# design.net
KiCad netlist of a schematic drawn in Altium Designer
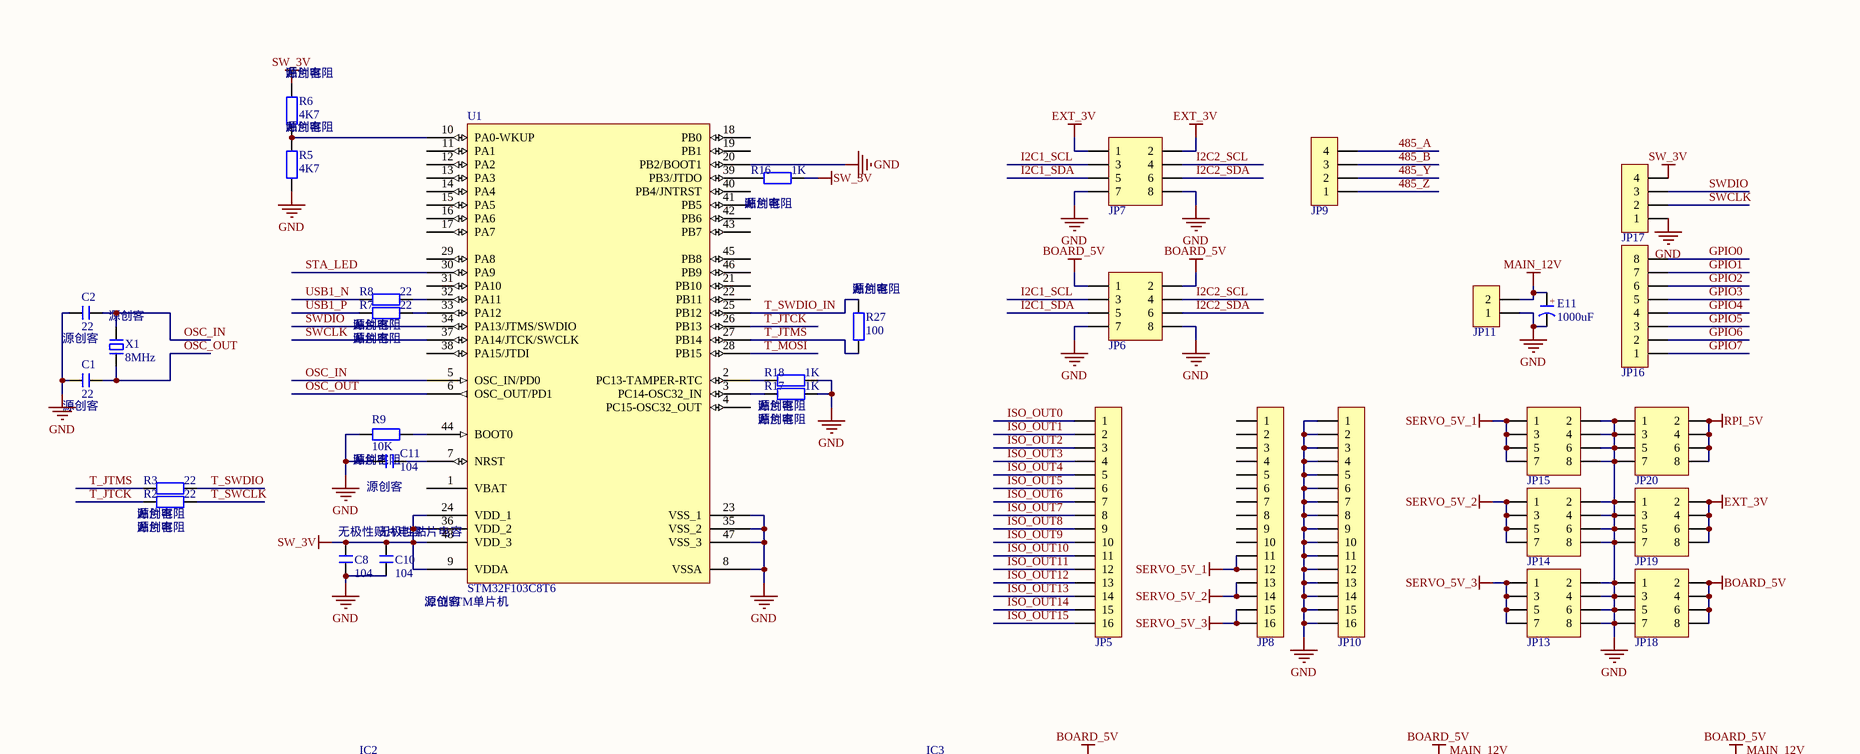
[diagram p0: 主板.SchDoc, top left]
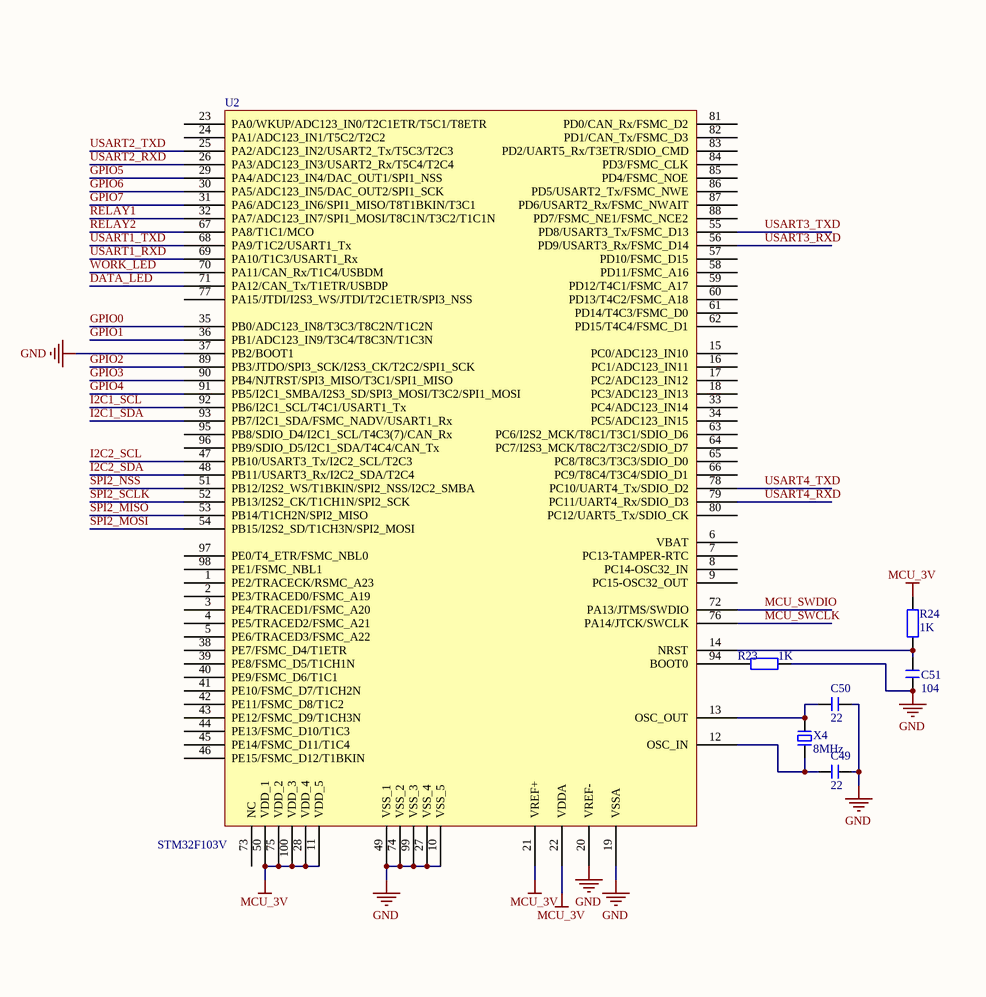
[diagram p1: 主板.SchDoc, top right]
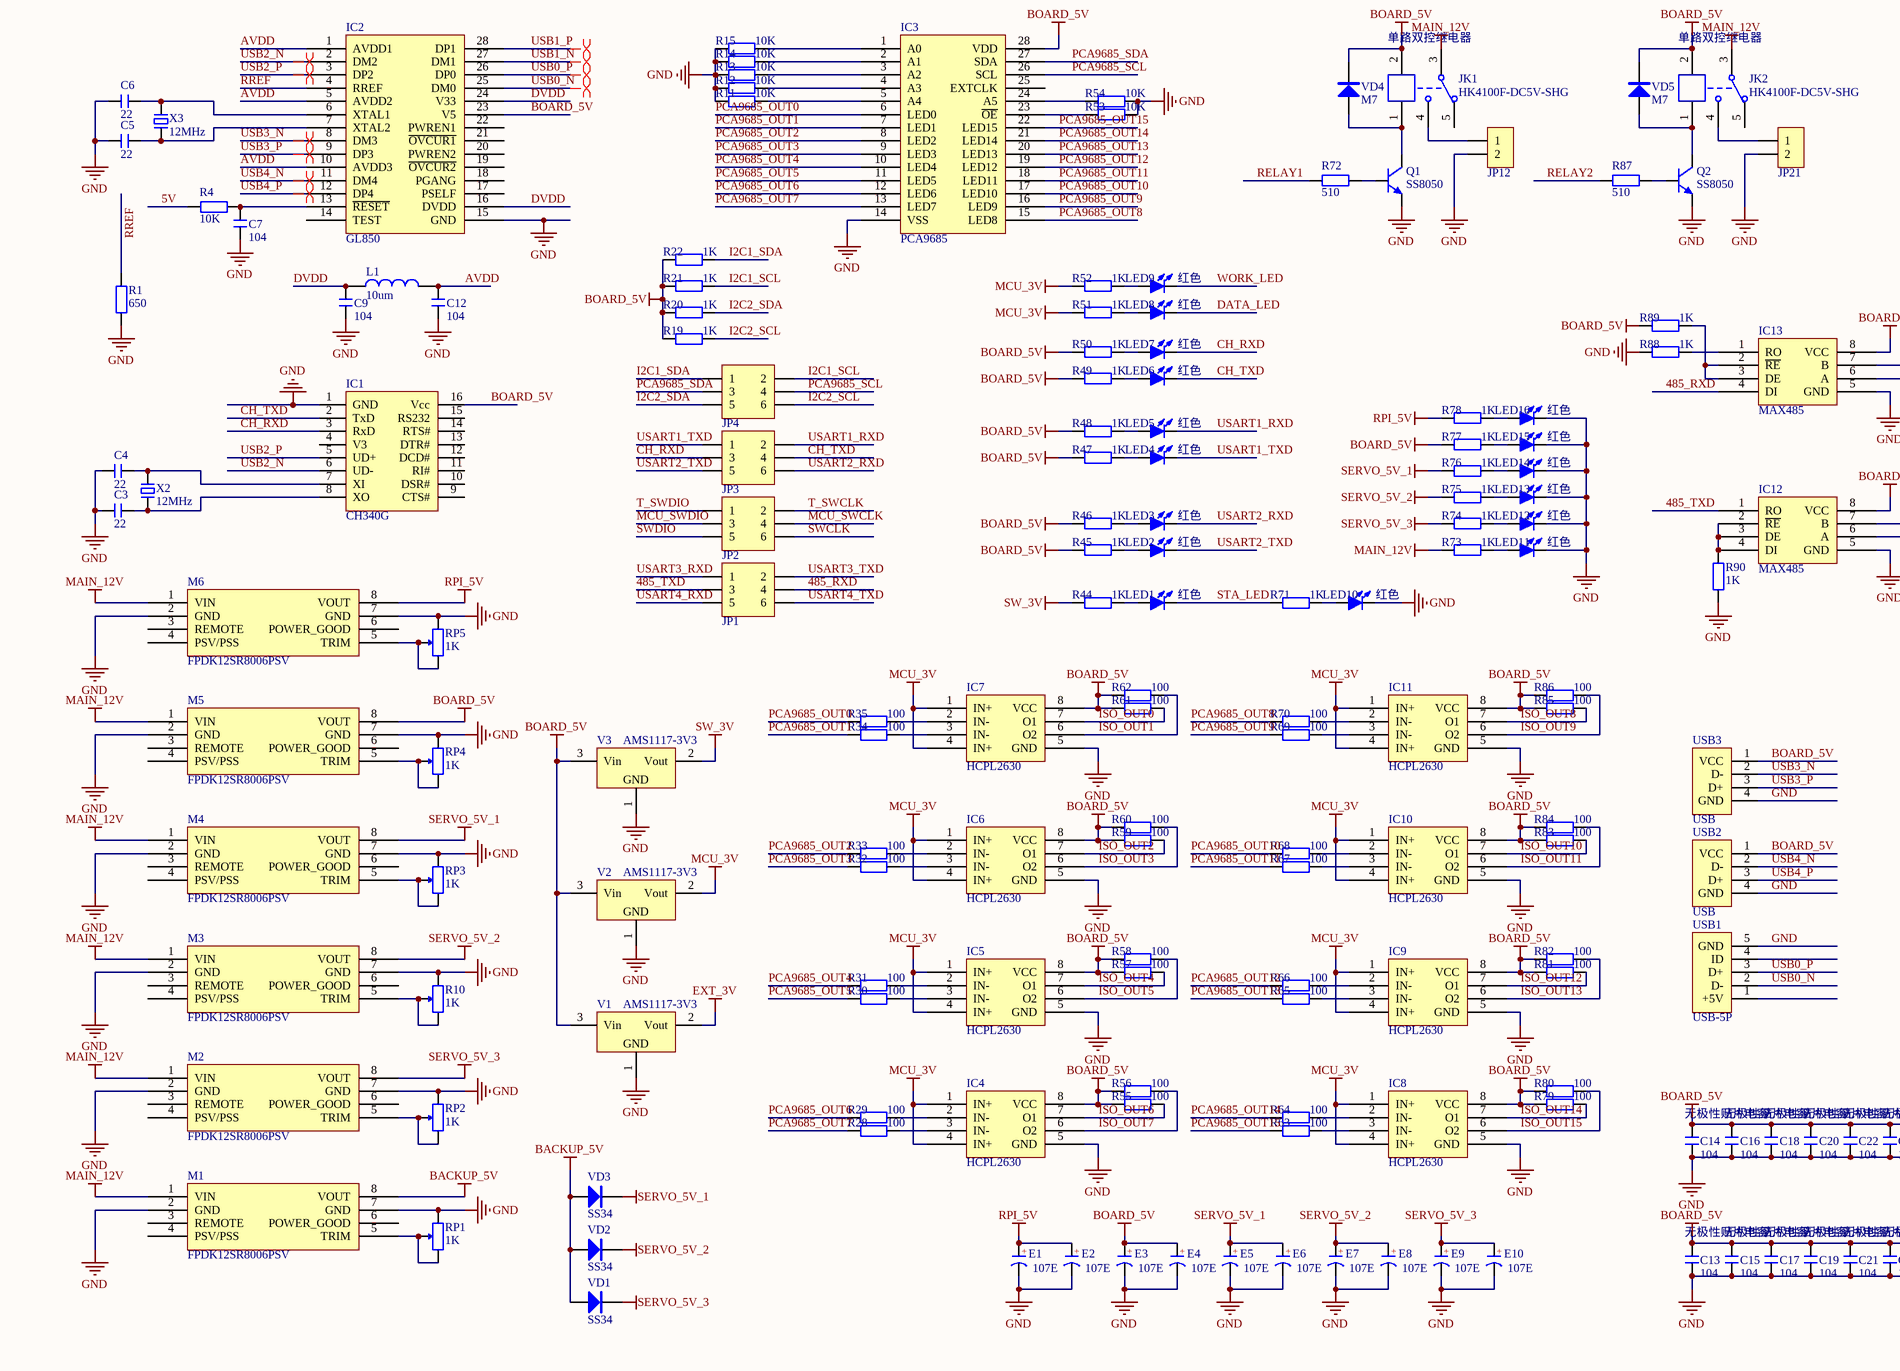
[diagram p2: 主板.SchDoc, bottom left]
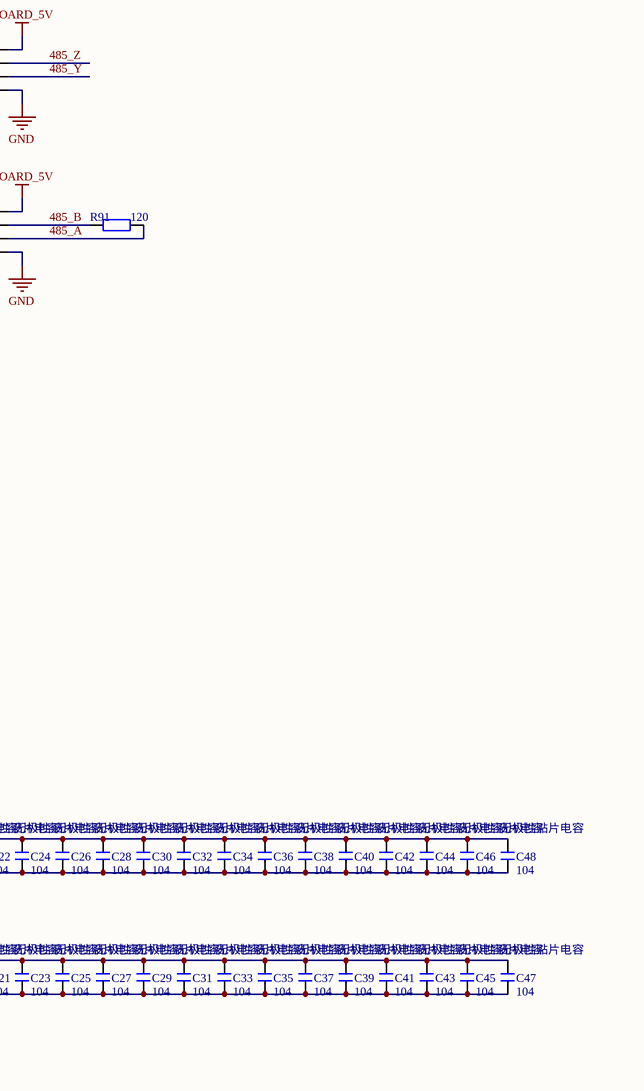
[diagram p3: 主板.SchDoc, bottom right]

(export (version "E")
  (design (tool "Eeschema 10.0.6"))
  (components
    (comp (ref "C1") (value "22") (description "无极性贴片电容") (libsource (lib "电阻-电容-电感") (part "C")))
    (comp (ref "C2") (value "22") (description "无极性贴片电容") (libsource (lib "电阻-电容-电感") (part "C")))
    (comp (ref "C3") (value "22") (description "无极性贴片电容") (libsource (lib "电阻-电容-电感") (part "C")))
    (comp (ref "C4") (value "22") (description "无极性贴片电容") (libsource (lib "电阻-电容-电感") (part "C")))
    (comp (ref "C5") (value "22") (description "无极性贴片电容") (libsource (lib "电阻-电容-电感") (part "C")))
    (comp (ref "C6") (value "22") (description "无极性贴片电容") (libsource (lib "电阻-电容-电感") (part "C")))
    (comp (ref "C7") (value "104") (description "无极性贴片电容") (libsource (lib "电阻-电容-电感") (part "C")))
    (comp (ref "C8") (value "104") (description "无极性贴片电容") (libsource (lib "电阻-电容-电感") (part "C")))
    (comp (ref "C9") (value "104") (description "无极性贴片电容") (libsource (lib "电阻-电容-电感") (part "C")))
    (comp (ref "C10") (value "104") (description "无极性贴片电容") (libsource (lib "电阻-电容-电感") (part "C")))
    (comp (ref "C11") (value "104") (description "无极性贴片电容") (libsource (lib "电阻-电容-电感") (part "C")))
    (comp (ref "C12") (value "104") (description "无极性贴片电容") (libsource (lib "电阻-电容-电感") (part "C")))
    (comp (ref "C13") (value "104") (description "无极性贴片电容") (libsource (lib "电阻-电容-电感") (part "C")))
    (comp (ref "C14") (value "104") (description "无极性贴片电容") (libsource (lib "电阻-电容-电感") (part "C")))
    (comp (ref "C15") (value "104") (description "无极性贴片电容") (libsource (lib "电阻-电容-电感") (part "C")))
    (comp (ref "C16") (value "104") (description "无极性贴片电容") (libsource (lib "电阻-电容-电感") (part "C")))
    (comp (ref "C17") (value "104") (description "无极性贴片电容") (libsource (lib "电阻-电容-电感") (part "C")))
    (comp (ref "C18") (value "104") (description "无极性贴片电容") (libsource (lib "电阻-电容-电感") (part "C")))
    (comp (ref "C19") (value "104") (description "无极性贴片电容") (libsource (lib "电阻-电容-电感") (part "C")))
    (comp (ref "C20") (value "104") (description "无极性贴片电容") (libsource (lib "电阻-电容-电感") (part "C")))
    (comp (ref "C21") (value "104") (description "无极性贴片电容") (libsource (lib "电阻-电容-电感") (part "C")))
    (comp (ref "C22") (value "104") (description "无极性贴片电容") (libsource (lib "电阻-电容-电感") (part "C")))
    (comp (ref "C23") (value "104") (description "无极性贴片电容") (libsource (lib "电阻-电容-电感") (part "C")))
    (comp (ref "C24") (value "104") (description "无极性贴片电容") (libsource (lib "电阻-电容-电感") (part "C")))
    (comp (ref "C25") (value "104") (description "无极性贴片电容") (libsource (lib "电阻-电容-电感") (part "C")))
    (comp (ref "C26") (value "104") (description "无极性贴片电容") (libsource (lib "电阻-电容-电感") (part "C")))
    (comp (ref "C27") (value "104") (description "无极性贴片电容") (libsource (lib "电阻-电容-电感") (part "C")))
    (comp (ref "C28") (value "104") (description "无极性贴片电容") (libsource (lib "电阻-电容-电感") (part "C")))
    (comp (ref "C29") (value "104") (description "无极性贴片电容") (libsource (lib "电阻-电容-电感") (part "C")))
    (comp (ref "C30") (value "104") (description "无极性贴片电容") (libsource (lib "电阻-电容-电感") (part "C")))
    (comp (ref "C31") (value "104") (description "无极性贴片电容") (libsource (lib "电阻-电容-电感") (part "C")))
    (comp (ref "C32") (value "104") (description "无极性贴片电容") (libsource (lib "电阻-电容-电感") (part "C")))
    (comp (ref "C33") (value "104") (description "无极性贴片电容") (libsource (lib "电阻-电容-电感") (part "C")))
    (comp (ref "C34") (value "104") (description "无极性贴片电容") (libsource (lib "电阻-电容-电感") (part "C")))
    (comp (ref "C35") (value "104") (description "无极性贴片电容") (libsource (lib "电阻-电容-电感") (part "C")))
    (comp (ref "C36") (value "104") (description "无极性贴片电容") (libsource (lib "电阻-电容-电感") (part "C")))
    (comp (ref "C37") (value "104") (description "无极性贴片电容") (libsource (lib "电阻-电容-电感") (part "C")))
    (comp (ref "C38") (value "104") (description "无极性贴片电容") (libsource (lib "电阻-电容-电感") (part "C")))
    (comp (ref "C39") (value "104") (description "无极性贴片电容") (libsource (lib "电阻-电容-电感") (part "C")))
    (comp (ref "C40") (value "104") (description "无极性贴片电容") (libsource (lib "电阻-电容-电感") (part "C")))
    (comp (ref "C41") (value "104") (description "无极性贴片电容") (libsource (lib "电阻-电容-电感") (part "C")))
    (comp (ref "C42") (value "104") (description "无极性贴片电容") (libsource (lib "电阻-电容-电感") (part "C")))
    (comp (ref "C43") (value "104") (description "无极性贴片电容") (libsource (lib "电阻-电容-电感") (part "C")))
    (comp (ref "C44") (value "104") (description "无极性贴片电容") (libsource (lib "电阻-电容-电感") (part "C")))
    (comp (ref "C45") (value "104") (description "无极性贴片电容") (libsource (lib "电阻-电容-电感") (part "C")))
    (comp (ref "C46") (value "104") (description "无极性贴片电容") (libsource (lib "电阻-电容-电感") (part "C")))
    (comp (ref "C47") (value "104") (description "无极性贴片电容") (libsource (lib "电阻-电容-电感") (part "C")))
    (comp (ref "C48") (value "104") (description "无极性贴片电容") (libsource (lib "电阻-电容-电感") (part "C")))
    (comp (ref "C49") (value "22") (description "无极性贴片电容") (libsource (lib "电阻-电容-电感") (part "C")))
    (comp (ref "C50") (value "22") (description "无极性贴片电容") (libsource (lib "电阻-电容-电感") (part "C")))
    (comp (ref "C51") (value "104") (description "无极性贴片电容") (libsource (lib "电阻-电容-电感") (part "C")))
    (comp (ref "E1") (value "107E") (description "贴片钽电容") (libsource (lib "电阻-电容-电感") (part "C-CD")))
    (comp (ref "E2") (value "107E") (description "贴片钽电容") (libsource (lib "电阻-电容-电感") (part "C-CD")))
    (comp (ref "E3") (value "107E") (description "贴片钽电容") (libsource (lib "电阻-电容-电感") (part "C-CD")))
    (comp (ref "E4") (value "107E") (description "贴片钽电容") (libsource (lib "电阻-电容-电感") (part "C-CD")))
    (comp (ref "E5") (value "107E") (description "贴片钽电容") (libsource (lib "电阻-电容-电感") (part "C-CD")))
    (comp (ref "E6") (value "107E") (description "贴片钽电容") (libsource (lib "电阻-电容-电感") (part "C-CD")))
    (comp (ref "E7") (value "107E") (description "贴片钽电容") (libsource (lib "电阻-电容-电感") (part "C-CD")))
    (comp (ref "E8") (value "107E") (description "贴片钽电容") (libsource (lib "电阻-电容-电感") (part "C-CD")))
    (comp (ref "E9") (value "107E") (description "贴片钽电容") (libsource (lib "电阻-电容-电感") (part "C-CD")))
    (comp (ref "E10") (value "107E") (description "贴片钽电容") (libsource (lib "电阻-电容-电感") (part "C-CD")))
    (comp (ref "E11") (value "1000uF") (description "直插固态电容") (libsource (lib "电阻-电容-电感") (part "C-CS")))
    (comp (ref "IC1") (value "CH340G") (description "串口转USB") (libsource (lib "IC芯片") (part "CH340G")))
    (comp (ref "IC2") (value "GL850") (description "4 Port USB HUB") (libsource (lib "ROV") (part "GL850G")))
    (comp (ref "IC3") (value "PCA9685") (libsource (lib "ROV") (part "PCA9685")))
    (comp (ref "IC4")
      (value "HCPL2630")
      (description "高速光电耦合器 10Mbit/s")
      (libsource (lib "ROV") (part "HCPL2630"))
    )
    (comp (ref "IC5")
      (value "HCPL2630")
      (description "高速光电耦合器 10Mbit/s")
      (libsource (lib "ROV") (part "HCPL2630"))
    )
    (comp (ref "IC6")
      (value "HCPL2630")
      (description "高速光电耦合器 10Mbit/s")
      (libsource (lib "ROV") (part "HCPL2630"))
    )
    (comp (ref "IC7")
      (value "HCPL2630")
      (description "高速光电耦合器 10Mbit/s")
      (libsource (lib "ROV") (part "HCPL2630"))
    )
    (comp (ref "IC8")
      (value "HCPL2630")
      (description "高速光电耦合器 10Mbit/s")
      (libsource (lib "ROV") (part "HCPL2630"))
    )
    (comp (ref "IC9")
      (value "HCPL2630")
      (description "高速光电耦合器 10Mbit/s")
      (libsource (lib "ROV") (part "HCPL2630"))
    )
    (comp (ref "IC10")
      (value "HCPL2630")
      (description "高速光电耦合器 10Mbit/s")
      (libsource (lib "ROV") (part "HCPL2630"))
    )
    (comp (ref "IC11")
      (value "HCPL2630")
      (description "高速光电耦合器 10Mbit/s")
      (libsource (lib "ROV") (part "HCPL2630"))
    )
    (comp (ref "IC12") (value "MAX485") (description "485通信芯片") (libsource (lib "ROV") (part "MAX485")))
    (comp (ref "IC13") (value "MAX485") (description "485通信芯片") (libsource (lib "ROV") (part "MAX485")))
    (comp (ref "JK1")
      (value "HK4100F-DC5V-SHG")
      (footprint "HK4100F")
      (description "单路双控继电器")
      (libsource (lib "继电器") (part "HK4100F"))
    )
    (comp (ref "JK2")
      (value "HK4100F-DC5V-SHG")
      (footprint "HK4100F")
      (description "单路双控继电器")
      (libsource (lib "继电器") (part "HK4100F"))
    )
    (comp (ref "JP1") (value "Header3X2") (description "3*2P接插件") (libsource (lib "接插件") (part "Header 3X2")))
    (comp (ref "JP2") (value "Header3X2") (description "3*2P接插件") (libsource (lib "接插件") (part "Header 3X2")))
    (comp (ref "JP3") (value "Header3X2") (description "3*2P接插件") (libsource (lib "接插件") (part "Header 3X2")))
    (comp (ref "JP4") (value "Header3X2") (description "3*2P接插件") (libsource (lib "接插件") (part "Header 3X2")))
    (comp (ref "JP5") (value "HDR-1X16") (description "16P接插件") (libsource (lib "接插件") (part "Header 16")))
    (comp (ref "JP6")
      (value "Header 4X2")
      (description "4*2P接插件")
      (libsource (lib "接插件") (part "Header 4X2"))
    )
    (comp (ref "JP7")
      (value "Header 4X2")
      (description "4*2P接插件")
      (libsource (lib "接插件") (part "Header 4X2"))
    )
    (comp (ref "JP8") (value "HDR-1X16") (description "16P接插件") (libsource (lib "接插件") (part "Header 16")))
    (comp (ref "JP9") (value "HDR-1X4") (description "4P接插件") (libsource (lib "接插件") (part "Header 4")))
    (comp (ref "JP10") (value "HDR-1X16") (description "16P接插件") (libsource (lib "接插件") (part "Header 16")))
    (comp (ref "JP11") (value "HDR-1X2") (description "2P接插件") (libsource (lib "接插件") (part "Header 2")))
    (comp (ref "JP12") (value "HDR-1X2") (description "2P接插件") (libsource (lib "") (part "Header 2_1")))
    (comp (ref "JP13")
      (value "Header 4X2")
      (description "4*2P接插件")
      (libsource (lib "接插件") (part "Header 4X2"))
    )
    (comp (ref "JP14")
      (value "Header 4X2")
      (description "4*2P接插件")
      (libsource (lib "接插件") (part "Header 4X2"))
    )
    (comp (ref "JP15")
      (value "Header 4X2")
      (description "4*2P接插件")
      (libsource (lib "接插件") (part "Header 4X2"))
    )
    (comp (ref "JP16") (value "HDR-1X8") (description "8P接插件") (libsource (lib "接插件") (part "Header 8")))
    (comp (ref "JP17") (value "HDR-1X4") (description "4P接插件") (libsource (lib "接插件") (part "Header 4")))
    (comp (ref "JP18")
      (value "Header 4X2")
      (description "4*2P接插件")
      (libsource (lib "接插件") (part "Header 4X2"))
    )
    (comp (ref "JP19")
      (value "Header 4X2")
      (description "4*2P接插件")
      (libsource (lib "接插件") (part "Header 4X2"))
    )
    (comp (ref "JP20")
      (value "Header 4X2")
      (description "4*2P接插件")
      (libsource (lib "接插件") (part "Header 4X2"))
    )
    (comp (ref "JP21") (value "HDR-1X2") (description "2P接插件") (libsource (lib "") (part "Header 2_1")))
    (comp (ref "L1") (value "10um") (description "小功率贴片电感") (libsource (lib "电阻-电容-电感") (part "L")))
    (comp (ref "LED1") (value "红色") (description "贴片LED") (libsource (lib "LED") (part "LED-SMD")))
    (comp (ref "LED2") (value "红色") (description "贴片LED") (libsource (lib "LED") (part "LED-SMD")))
    (comp (ref "LED3") (value "红色") (description "贴片LED") (libsource (lib "LED") (part "LED-SMD")))
    (comp (ref "LED4") (value "红色") (description "贴片LED") (libsource (lib "LED") (part "LED-SMD")))
    (comp (ref "LED5") (value "红色") (description "贴片LED") (libsource (lib "LED") (part "LED-SMD")))
    (comp (ref "LED6") (value "红色") (description "贴片LED") (libsource (lib "LED") (part "LED-SMD")))
    (comp (ref "LED7") (value "红色") (description "贴片LED") (libsource (lib "LED") (part "LED-SMD")))
    (comp (ref "LED8") (value "红色") (description "贴片LED") (libsource (lib "LED") (part "LED-SMD")))
    (comp (ref "LED9") (value "红色") (description "贴片LED") (libsource (lib "LED") (part "LED-SMD")))
    (comp (ref "LED10") (value "红色") (description "贴片LED") (libsource (lib "LED") (part "LED-SMD")))
    (comp (ref "LED11") (value "红色") (description "贴片LED") (libsource (lib "LED") (part "LED-SMD")))
    (comp (ref "LED12") (value "红色") (description "贴片LED") (libsource (lib "LED") (part "LED-SMD")))
    (comp (ref "LED13") (value "红色") (description "贴片LED") (libsource (lib "LED") (part "LED-SMD")))
    (comp (ref "LED14") (value "红色") (description "贴片LED") (libsource (lib "LED") (part "LED-SMD")))
    (comp (ref "LED15") (value "红色") (description "贴片LED") (libsource (lib "LED") (part "LED-SMD")))
    (comp (ref "LED16") (value "红色") (description "贴片LED") (libsource (lib "LED") (part "LED-SMD")))
    (comp (ref "M1")
      (value "FPDK12SR8006PSV")
      (footprint "FPDK12SR8006PSV")
      (description "DC-DC POWER CONVERTOR 12V-TO-5V")
      (libsource (lib "ROV") (part "FPDK12SR8006PSV"))
    )
    (comp (ref "M2")
      (value "FPDK12SR8006PSV")
      (footprint "FPDK12SR8006PSV")
      (description "DC-DC POWER CONVERTOR 12V-TO-5V")
      (libsource (lib "ROV") (part "FPDK12SR8006PSV"))
    )
    (comp (ref "M3")
      (value "FPDK12SR8006PSV")
      (footprint "FPDK12SR8006PSV")
      (description "DC-DC POWER CONVERTOR 12V-TO-5V")
      (libsource (lib "ROV") (part "FPDK12SR8006PSV"))
    )
    (comp (ref "M4")
      (value "FPDK12SR8006PSV")
      (footprint "FPDK12SR8006PSV")
      (description "DC-DC POWER CONVERTOR 12V-TO-5V")
      (libsource (lib "ROV") (part "FPDK12SR8006PSV"))
    )
    (comp (ref "M5")
      (value "FPDK12SR8006PSV")
      (footprint "FPDK12SR8006PSV")
      (description "DC-DC POWER CONVERTOR 12V-TO-5V")
      (libsource (lib "ROV") (part "FPDK12SR8006PSV"))
    )
    (comp (ref "M6")
      (value "FPDK12SR8006PSV")
      (footprint "FPDK12SR8006PSV")
      (description "DC-DC POWER CONVERTOR 12V-TO-5V")
      (libsource (lib "ROV") (part "FPDK12SR8006PSV"))
    )
    (comp (ref "Q1") (value "SS8050") (description "高频放大-NPN型") (libsource (lib "三极管") (part "8050-SMD")))
    (comp (ref "Q2") (value "SS8050") (description "高频放大-NPN型") (libsource (lib "三极管") (part "8050-SMD")))
    (comp (ref "R1") (value "650") (description "贴片电阻") (libsource (lib "电阻-电容-电感") (part "R")))
    (comp (ref "R2") (value "22") (description "贴片电阻") (libsource (lib "电阻-电容-电感") (part "R")))
    (comp (ref "R3") (value "22") (description "贴片电阻") (libsource (lib "电阻-电容-电感") (part "R")))
    (comp (ref "R4") (value "10K") (description "贴片电阻") (libsource (lib "电阻-电容-电感") (part "R")))
    (comp (ref "R5") (value "4K7") (description "贴片电阻") (libsource (lib "电阻-电容-电感") (part "R")))
    (comp (ref "R6") (value "4K7") (description "贴片电阻") (libsource (lib "电阻-电容-电感") (part "R")))
    (comp (ref "R7") (value "22") (description "贴片电阻") (libsource (lib "电阻-电容-电感") (part "R")))
    (comp (ref "R8") (value "22") (description "贴片电阻") (libsource (lib "电阻-电容-电感") (part "R")))
    (comp (ref "R9") (value "10K") (description "贴片电阻") (libsource (lib "电阻-电容-电感") (part "R")))
    (comp (ref "R10")
      (value "1K")
      (footprint "3296W")
      (description "插件单联电位器")
      (libsource (lib "电阻-电容-电感") (part "RP-ID"))
    )
    (comp (ref "R11") (value "10K") (description "贴片电阻") (libsource (lib "电阻-电容-电感") (part "R")))
    (comp (ref "R12") (value "10K") (description "贴片电阻") (libsource (lib "电阻-电容-电感") (part "R")))
    (comp (ref "R13") (value "10K") (description "贴片电阻") (libsource (lib "电阻-电容-电感") (part "R")))
    (comp (ref "R14") (value "10K") (description "贴片电阻") (libsource (lib "电阻-电容-电感") (part "R")))
    (comp (ref "R15") (value "10K") (description "贴片电阻") (libsource (lib "电阻-电容-电感") (part "R")))
    (comp (ref "R16") (value "1K") (description "贴片电阻") (libsource (lib "电阻-电容-电感") (part "R")))
    (comp (ref "R17") (value "1K") (description "贴片电阻") (libsource (lib "电阻-电容-电感") (part "R")))
    (comp (ref "R18") (value "1K") (description "贴片电阻") (libsource (lib "电阻-电容-电感") (part "R")))
    (comp (ref "R19") (value "1K") (description "贴片电阻") (libsource (lib "电阻-电容-电感") (part "R")))
    (comp (ref "R20") (value "1K") (description "贴片电阻") (libsource (lib "电阻-电容-电感") (part "R")))
    (comp (ref "R21") (value "1K") (description "贴片电阻") (libsource (lib "电阻-电容-电感") (part "R")))
    (comp (ref "R22") (value "1K") (description "贴片电阻") (libsource (lib "电阻-电容-电感") (part "R")))
    (comp (ref "R23") (value "1K") (description "贴片电阻") (libsource (lib "电阻-电容-电感") (part "R")))
    (comp (ref "R24") (value "1K") (description "贴片电阻") (libsource (lib "电阻-电容-电感") (part "R")))
    (comp (ref "R27") (value "100") (description "贴片电阻") (libsource (lib "电阻-电容-电感") (part "R")))
    (comp (ref "R28") (value "100") (description "贴片电阻") (libsource (lib "电阻-电容-电感") (part "R")))
    (comp (ref "R29") (value "100") (description "贴片电阻") (libsource (lib "电阻-电容-电感") (part "R")))
    (comp (ref "R30") (value "100") (description "贴片电阻") (libsource (lib "电阻-电容-电感") (part "R")))
    (comp (ref "R31") (value "100") (description "贴片电阻") (libsource (lib "电阻-电容-电感") (part "R")))
    (comp (ref "R32") (value "100") (description "贴片电阻") (libsource (lib "电阻-电容-电感") (part "R")))
    (comp (ref "R33") (value "100") (description "贴片电阻") (libsource (lib "电阻-电容-电感") (part "R")))
    (comp (ref "R34") (value "100") (description "贴片电阻") (libsource (lib "电阻-电容-电感") (part "R")))
    (comp (ref "R35") (value "100") (description "贴片电阻") (libsource (lib "电阻-电容-电感") (part "R")))
    (comp (ref "R44") (value "1K") (description "贴片电阻") (libsource (lib "电阻-电容-电感") (part "R")))
    (comp (ref "R45") (value "1K") (description "贴片电阻") (libsource (lib "电阻-电容-电感") (part "R")))
    (comp (ref "R46") (value "1K") (description "贴片电阻") (libsource (lib "电阻-电容-电感") (part "R")))
    (comp (ref "R47") (value "1K") (description "贴片电阻") (libsource (lib "电阻-电容-电感") (part "R")))
    (comp (ref "R48") (value "1K") (description "贴片电阻") (libsource (lib "电阻-电容-电感") (part "R")))
    (comp (ref "R49") (value "1K") (description "贴片电阻") (libsource (lib "电阻-电容-电感") (part "R")))
    (comp (ref "R50") (value "1K") (description "贴片电阻") (libsource (lib "电阻-电容-电感") (part "R")))
    (comp (ref "R51") (value "1K") (description "贴片电阻") (libsource (lib "电阻-电容-电感") (part "R")))
    (comp (ref "R52") (value "1K") (description "贴片电阻") (libsource (lib "电阻-电容-电感") (part "R")))
    (comp (ref "R53") (value "10K") (description "贴片电阻") (libsource (lib "电阻-电容-电感") (part "R")))
    (comp (ref "R54") (value "10K") (description "贴片电阻") (libsource (lib "电阻-电容-电感") (part "R")))
    (comp (ref "R55") (value "100") (description "贴片电阻") (libsource (lib "电阻-电容-电感") (part "R")))
    (comp (ref "R56") (value "100") (description "贴片电阻") (libsource (lib "电阻-电容-电感") (part "R")))
    (comp (ref "R57") (value "100") (description "贴片电阻") (libsource (lib "电阻-电容-电感") (part "R")))
    (comp (ref "R58") (value "100") (description "贴片电阻") (libsource (lib "电阻-电容-电感") (part "R")))
    (comp (ref "R59") (value "100") (description "贴片电阻") (libsource (lib "电阻-电容-电感") (part "R")))
    (comp (ref "R60") (value "100") (description "贴片电阻") (libsource (lib "电阻-电容-电感") (part "R")))
    (comp (ref "R61") (value "100") (description "贴片电阻") (libsource (lib "电阻-电容-电感") (part "R")))
    (comp (ref "R62") (value "100") (description "贴片电阻") (libsource (lib "电阻-电容-电感") (part "R")))
    (comp (ref "R63") (value "100") (description "贴片电阻") (libsource (lib "电阻-电容-电感") (part "R")))
    (comp (ref "R64") (value "100") (description "贴片电阻") (libsource (lib "电阻-电容-电感") (part "R")))
    (comp (ref "R65") (value "100") (description "贴片电阻") (libsource (lib "电阻-电容-电感") (part "R")))
    (comp (ref "R66") (value "100") (description "贴片电阻") (libsource (lib "电阻-电容-电感") (part "R")))
    (comp (ref "R67") (value "100") (description "贴片电阻") (libsource (lib "电阻-电容-电感") (part "R")))
    (comp (ref "R68") (value "100") (description "贴片电阻") (libsource (lib "电阻-电容-电感") (part "R")))
    (comp (ref "R69") (value "100") (description "贴片电阻") (libsource (lib "电阻-电容-电感") (part "R")))
    (comp (ref "R70") (value "100") (description "贴片电阻") (libsource (lib "电阻-电容-电感") (part "R")))
    (comp (ref "R71") (value "1K") (description "贴片电阻") (libsource (lib "电阻-电容-电感") (part "R")))
    (comp (ref "R72") (value "510") (description "贴片电阻") (libsource (lib "电阻-电容-电感") (part "R")))
    (comp (ref "R73") (value "1K") (description "贴片电阻") (libsource (lib "电阻-电容-电感") (part "R")))
    (comp (ref "R74") (value "1K") (description "贴片电阻") (libsource (lib "电阻-电容-电感") (part "R")))
    (comp (ref "R75") (value "1K") (description "贴片电阻") (libsource (lib "电阻-电容-电感") (part "R")))
    (comp (ref "R76") (value "1K") (description "贴片电阻") (libsource (lib "电阻-电容-电感") (part "R")))
    (comp (ref "R77") (value "1K") (description "贴片电阻") (libsource (lib "电阻-电容-电感") (part "R")))
    (comp (ref "R78") (value "1K") (description "贴片电阻") (libsource (lib "电阻-电容-电感") (part "R")))
    (comp (ref "R79") (value "100") (description "贴片电阻") (libsource (lib "电阻-电容-电感") (part "R")))
    (comp (ref "R80") (value "100") (description "贴片电阻") (libsource (lib "电阻-电容-电感") (part "R")))
    (comp (ref "R81") (value "100") (description "贴片电阻") (libsource (lib "电阻-电容-电感") (part "R")))
    (comp (ref "R82") (value "100") (description "贴片电阻") (libsource (lib "电阻-电容-电感") (part "R")))
    (comp (ref "R83") (value "100") (description "贴片电阻") (libsource (lib "电阻-电容-电感") (part "R")))
    (comp (ref "R84") (value "100") (description "贴片电阻") (libsource (lib "电阻-电容-电感") (part "R")))
    (comp (ref "R85") (value "100") (description "贴片电阻") (libsource (lib "电阻-电容-电感") (part "R")))
    (comp (ref "R86") (value "100") (description "贴片电阻") (libsource (lib "电阻-电容-电感") (part "R")))
    (comp (ref "R87") (value "510") (description "贴片电阻") (libsource (lib "电阻-电容-电感") (part "R")))
    (comp (ref "R88") (value "1K") (description "贴片电阻") (libsource (lib "电阻-电容-电感") (part "R")))
    (comp (ref "R89") (value "1K") (description "贴片电阻") (libsource (lib "电阻-电容-电感") (part "R")))
    (comp (ref "R90") (value "1K") (description "贴片电阻") (libsource (lib "电阻-电容-电感") (part "R")))
    (comp (ref "R91") (value "120") (description "贴片电阻") (libsource (lib "电阻-电容-电感") (part "R")))
    (comp (ref "RP1")
      (value "1K")
      (footprint "3296W")
      (description "插件单联电位器")
      (libsource (lib "电阻-电容-电感") (part "RP-ID"))
    )
    (comp (ref "RP2")
      (value "1K")
      (footprint "3296W")
      (description "插件单联电位器")
      (libsource (lib "电阻-电容-电感") (part "RP-ID"))
    )
    (comp (ref "RP3")
      (value "1K")
      (footprint "3296W")
      (description "插件单联电位器")
      (libsource (lib "电阻-电容-电感") (part "RP-ID"))
    )
    (comp (ref "RP4")
      (value "1K")
      (footprint "3296W")
      (description "插件单联电位器")
      (libsource (lib "电阻-电容-电感") (part "RP-ID"))
    )
    (comp (ref "RP5")
      (value "1K")
      (footprint "3296W")
      (description "插件单联电位器")
      (libsource (lib "电阻-电容-电感") (part "RP-ID"))
    )
    (comp (ref "U1")
      (value "STM32F103C8T6")
      (description "Flaah:64/RAM:20/IO:36")
      (libsource (lib "STM32系列单片机") (part "STM32F103C8T6"))
    )
    (comp (ref "U2")
      (value "STM32F103V")
      (description "32位STM单片机100引脚")
      (libsource (lib "STM32系列单片机") (part "STM32F103V"))
    )
    (comp (ref "USB1") (value "USB-5P") (description "微型USB母座") (libsource (lib "接口类") (part "USB-5P")))
    (comp (ref "USB2") (value "USB") (description "USB-A型母接口") (libsource (lib "接口类") (part "USB-A/S")))
    (comp (ref "USB3") (value "USB") (description "USB-A型母接口") (libsource (lib "接口类") (part "USB-A/S")))
    (comp (ref "V1") (value "AMS1117-3V3") (description "三端稳压芯片") (libsource (lib "IC芯片") (part "AMS1117")))
    (comp (ref "V2") (value "AMS1117-3V3") (description "三端稳压芯片") (libsource (lib "IC芯片") (part "AMS1117")))
    (comp (ref "V3") (value "AMS1117-3V3") (description "三端稳压芯片") (libsource (lib "IC芯片") (part "AMS1117")))
    (comp (ref "VD1") (value "SS34") (description "肖特基二极管") (libsource (lib "二极管-整流桥") (part "SS34")))
    (comp (ref "VD2") (value "SS34") (description "肖特基二极管") (libsource (lib "二极管-整流桥") (part "SS34")))
    (comp (ref "VD3") (value "SS34") (description "肖特基二极管") (libsource (lib "二极管-整流桥") (part "SS34")))
    (comp (ref "VD4") (value "M7") (description "整流二极管") (libsource (lib "二极管-整流桥") (part "M7")))
    (comp (ref "VD5") (value "M7") (description "整流二极管") (libsource (lib "二极管-整流桥") (part "M7")))
    (comp (ref "X1")
      (value "8MHz")
      (footprint "XTAL-49S DIP")
      (description "2脚晶振")
      (libsource (lib "保险丝-晶振") (part "XTAL-2"))
    )
    (comp (ref "X2")
      (value "12MHz")
      (footprint "XTAL-49S DIP")
      (description "2脚晶振")
      (libsource (lib "保险丝-晶振") (part "XTAL-2"))
    )
    (comp (ref "X3")
      (value "12MHz")
      (footprint "XTAL-49S DIP")
      (description "2脚晶振")
      (libsource (lib "保险丝-晶振") (part "XTAL-2"))
    )
    (comp (ref "X4")
      (value "8MHz")
      (footprint "XTAL-49S DIP")
      (description "2脚晶振")
      (libsource (lib "保险丝-晶振") (part "XTAL-2"))
    )
  )
  (nets
    (net (code "1") (name "/5V") (class "Default")
      (node (ref "R4") (pin "1") (pinfunction "1_1") (pintype "passive"))
    )
    (net (code "2") (name "/485_A") (class "Default")
      (node (ref "IC12") (pin "6") (pinfunction "A_6") (pintype "passive"))
      (node (ref "JP9") (pin "4") (pinfunction "4_4") (pintype "passive"))
      (node (ref "R91") (pin "1") (pinfunction "1_1") (pintype "passive"))
    )
    (net (code "3") (name "/485_B") (class "Default")
      (node (ref "IC12") (pin "7") (pinfunction "B_7") (pintype "passive"))
      (node (ref "JP9") (pin "3") (pinfunction "3_3") (pintype "passive"))
      (node (ref "R91") (pin "2") (pinfunction "2_2") (pintype "passive"))
    )
    (net (code "4") (name "/485_RXD") (class "Default")
      (node (ref "IC13") (pin "4") (pinfunction "DI_4") (pintype "passive"))
      (node (ref "JP1") (pin "4") (pinfunction "4_4") (pintype "passive"))
    )
    (net (code "5") (name "/485_TXD") (class "Default")
      (node (ref "IC12") (pin "1") (pinfunction "RO_1") (pintype "passive"))
      (node (ref "JP1") (pin "3") (pinfunction "3_3") (pintype "passive"))
    )
    (net (code "6") (name "/485_Y") (class "Default")
      (node (ref "IC13") (pin "6") (pinfunction "A_6") (pintype "passive"))
      (node (ref "JP9") (pin "2") (pinfunction "2_2") (pintype "passive"))
    )
    (net (code "7") (name "/485_Z") (class "Default")
      (node (ref "IC13") (pin "7") (pinfunction "B_7") (pintype "passive"))
      (node (ref "JP9") (pin "1") (pinfunction "1_1") (pintype "passive"))
    )
    (net (code "8") (name "/AVDD") (class "Default")
      (node (ref "C12") (pin "2") (pinfunction "2_2") (pintype "passive"))
      (node (ref "IC2") (pin "1") (pinfunction "AVDD1_1") (pintype "passive"))
      (node (ref "IC2") (pin "10") (pinfunction "AVDD3_10") (pintype "passive"))
      (node (ref "IC2") (pin "5") (pinfunction "AVDD2_5") (pintype "passive"))
      (node (ref "L1") (pin "2") (pinfunction "2_2") (pintype "passive"))
    )
    (net (code "9") (name "/CH_RXD") (class "Default")
      (node (ref "IC1") (pin "3") (pinfunction "RxD_3") (pintype "passive"))
      (node (ref "JP3") (pin "3") (pinfunction "3_3") (pintype "passive"))
      (node (ref "LED7") (pin "2") (pinfunction "K_2") (pintype "passive"))
    )
    (net (code "10") (name "/CH_TXD") (class "Default")
      (node (ref "IC1") (pin "2") (pinfunction "TxD_2") (pintype "passive"))
      (node (ref "JP3") (pin "4") (pinfunction "4_4") (pintype "passive"))
      (node (ref "LED6") (pin "2") (pinfunction "K_2") (pintype "passive"))
    )
    (net (code "11") (name "/DATA_LED") (class "Default")
      (node (ref "LED8") (pin "2") (pinfunction "K_2") (pintype "passive"))
      (node (ref "U2") (pin "71") (pinfunction "PA12/CAN_Tx/T1ETR/USBDP_71") (pintype "passive"))
    )
    (net (code "12") (name "/DVDD") (class "Default")
      (node (ref "C9") (pin "2") (pinfunction "2_2") (pintype "passive"))
      (node (ref "IC2") (pin "16") (pinfunction "DVDD_16") (pintype "passive"))
      (node (ref "IC2") (pin "24") (pinfunction "V33_24") (pintype "passive"))
      (node (ref "L1") (pin "1") (pinfunction "1_1") (pintype "passive"))
    )
    (net (code "13") (name "/GPIO0") (class "Default")
      (node (ref "JP16") (pin "8") (pinfunction "8_8") (pintype "passive"))
      (node (ref "U2") (pin "35") (pinfunction "PB0/ADC123_IN8/T3C3/T8C2N/T1C2N_35") (pintype "passive"))
    )
    (net (code "14") (name "/GPIO1") (class "Default")
      (node (ref "JP16") (pin "7") (pinfunction "7_7") (pintype "passive"))
      (node (ref "U2") (pin "36") (pinfunction "PB1/ADC123_IN9/T3C4/T8C3N/T1C3N_36") (pintype "passive"))
    )
    (net (code "15") (name "/GPIO2") (class "Default")
      (node (ref "JP16") (pin "6") (pinfunction "6_6") (pintype "passive"))
      (node (ref "U2") (pin "89") (pinfunction "PB3/JTDO/SPI3_SCK/I2S3_CK/T2C2/SPI1_SCK_89") (pintype "passive"))
    )
    (net (code "16") (name "/GPIO3") (class "Default")
      (node (ref "JP16") (pin "5") (pinfunction "5_5") (pintype "passive"))
      (node (ref "U2") (pin "90") (pinfunction "PB4/NJTRST/SPI3_MISO/T3C1/SPI1_MISO_90") (pintype "passive"))
    )
    (net (code "17") (name "/GPIO4") (class "Default")
      (node (ref "JP16") (pin "4") (pinfunction "4_4") (pintype "passive"))
      (node (ref "U2") (pin "91") (pinfunction "PB5/I2C1_SMBA/I2S3_SD/SPI3_MOSI/T3C2/SPI1_MOSI_91") (pintype "passive"))
    )
    (net (code "18") (name "/GPIO5") (class "Default")
      (node (ref "JP16") (pin "3") (pinfunction "3_3") (pintype "passive"))
      (node (ref "U2") (pin "29") (pinfunction "PA4/ADC123_IN4/DAC_OUT1/SPI1_NSS_29") (pintype "passive"))
    )
    (net (code "19") (name "/GPIO6") (class "Default")
      (node (ref "JP16") (pin "2") (pinfunction "2_2") (pintype "passive"))
      (node (ref "U2") (pin "30") (pinfunction "PA5/ADC123_IN5/DAC_OUT2/SPI1_SCK_30") (pintype "passive"))
    )
    (net (code "20") (name "/GPIO7") (class "Default")
      (node (ref "JP16") (pin "1") (pinfunction "1_1") (pintype "passive"))
      (node (ref "U2") (pin "31") (pinfunction "PA6/ADC123_IN6/SPI1_MISO/T8T1BKIN/T3C1_31") (pintype "passive"))
    )
    (net (code "21") (name "/I2C1_SCL") (class "Default")
      (node (ref "JP4") (pin "2") (pinfunction "2_2") (pintype "passive"))
      (node (ref "JP6") (pin "3") (pinfunction "3_3") (pintype "passive"))
      (node (ref "JP7") (pin "3") (pinfunction "3_3") (pintype "passive"))
      (node (ref "R21") (pin "1") (pinfunction "1_1") (pintype "passive"))
      (node (ref "U2") (pin "92") (pinfunction "PB6/I2C1_SCL/T4C1/USART1_Tx_92") (pintype "passive"))
    )
    (net (code "22") (name "/I2C1_SDA") (class "Default")
      (node (ref "JP4") (pin "1") (pinfunction "1_1") (pintype "passive"))
      (node (ref "JP6") (pin "5") (pinfunction "5_5") (pintype "passive"))
      (node (ref "JP7") (pin "5") (pinfunction "5_5") (pintype "passive"))
      (node (ref "R22") (pin "1") (pinfunction "1_1") (pintype "passive"))
      (node (ref "U2") (pin "93") (pinfunction "PB7/I2C1_SDA/FSMC_NADV/USART1_Rx_93") (pintype "passive"))
    )
    (net (code "23") (name "/I2C2_SCL") (class "Default")
      (node (ref "JP4") (pin "6") (pinfunction "6_6") (pintype "passive"))
      (node (ref "JP6") (pin "4") (pinfunction "4_4") (pintype "passive"))
      (node (ref "JP7") (pin "4") (pinfunction "4_4") (pintype "passive"))
      (node (ref "R19") (pin "1") (pinfunction "1_1") (pintype "passive"))
      (node (ref "U2") (pin "47") (pinfunction "PB10/USART3_Tx/I2C2_SCL/T2C3_47") (pintype "passive"))
    )
    (net (code "24") (name "/I2C2_SDA") (class "Default")
      (node (ref "JP4") (pin "5") (pinfunction "5_5") (pintype "passive"))
      (node (ref "JP6") (pin "6") (pinfunction "6_6") (pintype "passive"))
      (node (ref "JP7") (pin "6") (pinfunction "6_6") (pintype "passive"))
      (node (ref "R20") (pin "1") (pinfunction "1_1") (pintype "passive"))
      (node (ref "U2") (pin "48") (pinfunction "PB11/USART3_Rx/I2C2_SDA/T2C4_48") (pintype "passive"))
    )
    (net (code "25") (name "/ISO_OUT0") (class "Default")
      (node (ref "IC7") (pin "7") (pinfunction "O1_7") (pintype "passive"))
      (node (ref "JP5") (pin "1") (pinfunction "1_1") (pintype "passive"))
      (node (ref "R61") (pin "2") (pinfunction "2_2") (pintype "passive"))
    )
    (net (code "26") (name "/ISO_OUT1") (class "Default")
      (node (ref "IC7") (pin "6") (pinfunction "O2_6") (pintype "passive"))
      (node (ref "JP5") (pin "2") (pinfunction "2_2") (pintype "passive"))
      (node (ref "R62") (pin "2") (pinfunction "2_2") (pintype "passive"))
    )
    (net (code "27") (name "/ISO_OUT2") (class "Default")
      (node (ref "IC6") (pin "7") (pinfunction "O1_7") (pintype "passive"))
      (node (ref "JP5") (pin "3") (pinfunction "3_3") (pintype "passive"))
      (node (ref "R59") (pin "2") (pinfunction "2_2") (pintype "passive"))
    )
    (net (code "28") (name "/ISO_OUT3") (class "Default")
      (node (ref "IC6") (pin "6") (pinfunction "O2_6") (pintype "passive"))
      (node (ref "JP5") (pin "4") (pinfunction "4_4") (pintype "passive"))
      (node (ref "R60") (pin "2") (pinfunction "2_2") (pintype "passive"))
    )
    (net (code "29") (name "/ISO_OUT4") (class "Default")
      (node (ref "IC5") (pin "7") (pinfunction "O1_7") (pintype "passive"))
      (node (ref "JP5") (pin "5") (pinfunction "5_5") (pintype "passive"))
      (node (ref "R57") (pin "2") (pinfunction "2_2") (pintype "passive"))
    )
    (net (code "30") (name "/ISO_OUT5") (class "Default")
      (node (ref "IC5") (pin "6") (pinfunction "O2_6") (pintype "passive"))
      (node (ref "JP5") (pin "6") (pinfunction "6_6") (pintype "passive"))
      (node (ref "R58") (pin "2") (pinfunction "2_2") (pintype "passive"))
    )
    (net (code "31") (name "/ISO_OUT6") (class "Default")
      (node (ref "IC4") (pin "7") (pinfunction "O1_7") (pintype "passive"))
      (node (ref "JP5") (pin "7") (pinfunction "7_7") (pintype "passive"))
      (node (ref "R55") (pin "2") (pinfunction "2_2") (pintype "passive"))
    )
    (net (code "32") (name "/ISO_OUT7") (class "Default")
      (node (ref "IC4") (pin "6") (pinfunction "O2_6") (pintype "passive"))
      (node (ref "JP5") (pin "8") (pinfunction "8_8") (pintype "passive"))
      (node (ref "R56") (pin "2") (pinfunction "2_2") (pintype "passive"))
    )
    (net (code "33") (name "/ISO_OUT8") (class "Default")
      (node (ref "IC11") (pin "7") (pinfunction "O1_7") (pintype "passive"))
      (node (ref "JP5") (pin "9") (pinfunction "9_9") (pintype "passive"))
      (node (ref "R85") (pin "2") (pinfunction "2_2") (pintype "passive"))
    )
    (net (code "34") (name "/ISO_OUT9") (class "Default")
      (node (ref "IC11") (pin "6") (pinfunction "O2_6") (pintype "passive"))
      (node (ref "JP5") (pin "10") (pinfunction "10_10") (pintype "passive"))
      (node (ref "R86") (pin "2") (pinfunction "2_2") (pintype "passive"))
    )
    (net (code "35") (name "/ISO_OUT10") (class "Default")
      (node (ref "IC10") (pin "7") (pinfunction "O1_7") (pintype "passive"))
      (node (ref "JP5") (pin "11") (pinfunction "11_11") (pintype "passive"))
      (node (ref "R83") (pin "2") (pinfunction "2_2") (pintype "passive"))
    )
    (net (code "36") (name "/ISO_OUT11") (class "Default")
      (node (ref "IC10") (pin "6") (pinfunction "O2_6") (pintype "passive"))
      (node (ref "JP5") (pin "12") (pinfunction "12_12") (pintype "passive"))
      (node (ref "R84") (pin "2") (pinfunction "2_2") (pintype "passive"))
    )
    (net (code "37") (name "/ISO_OUT12") (class "Default")
      (node (ref "IC9") (pin "7") (pinfunction "O1_7") (pintype "passive"))
      (node (ref "JP5") (pin "13") (pinfunction "13_13") (pintype "passive"))
      (node (ref "R81") (pin "2") (pinfunction "2_2") (pintype "passive"))
    )
    (net (code "38") (name "/ISO_OUT13") (class "Default")
      (node (ref "IC9") (pin "6") (pinfunction "O2_6") (pintype "passive"))
      (node (ref "JP5") (pin "14") (pinfunction "14_14") (pintype "passive"))
      (node (ref "R82") (pin "2") (pinfunction "2_2") (pintype "passive"))
    )
    (net (code "39") (name "/ISO_OUT14") (class "Default")
      (node (ref "IC8") (pin "7") (pinfunction "O1_7") (pintype "passive"))
      (node (ref "JP5") (pin "15") (pinfunction "15_15") (pintype "passive"))
      (node (ref "R79") (pin "2") (pinfunction "2_2") (pintype "passive"))
    )
    (net (code "40") (name "/ISO_OUT15") (class "Default")
      (node (ref "IC8") (pin "6") (pinfunction "O2_6") (pintype "passive"))
      (node (ref "JP5") (pin "16") (pinfunction "16_16") (pintype "passive"))
      (node (ref "R80") (pin "2") (pinfunction "2_2") (pintype "passive"))
    )
    (net (code "41") (name "/MCU_SWCLK") (class "Default")
      (node (ref "JP2") (pin "4") (pinfunction "4_4") (pintype "passive"))
      (node (ref "U2") (pin "76") (pinfunction "PA14/JTCK/SWCLK_76") (pintype "passive"))
    )
    (net (code "42") (name "/MCU_SWDIO") (class "Default")
      (node (ref "JP2") (pin "3") (pinfunction "3_3") (pintype "passive"))
      (node (ref "U2") (pin "72") (pinfunction "PA13/JTMS/SWDIO_72") (pintype "passive"))
    )
    (net (code "43") (name "/OSC_IN") (class "Default")
      (node (ref "C2") (pin "2") (pinfunction "2_2") (pintype "passive"))
      (node (ref "U1") (pin "5") (pinfunction "OSC_IN/PD0_5") (pintype "input"))
      (node (ref "X1") (pin "2") (pinfunction "2_2") (pintype "passive"))
    )
    (net (code "44") (name "/OSC_OUT") (class "Default")
      (node (ref "C1") (pin "2") (pinfunction "2_2") (pintype "passive"))
      (node (ref "U1") (pin "6") (pinfunction "OSC_OUT/PD1_6") (pintype "output"))
      (node (ref "X1") (pin "1") (pinfunction "1_1") (pintype "passive"))
    )
    (net (code "45") (name "/PCA9685_OUT0") (class "Default")
      (node (ref "IC3") (pin "6") (pinfunction "LED0_6") (pintype "passive"))
      (node (ref "R35") (pin "1") (pinfunction "1_1") (pintype "passive"))
    )
    (net (code "46") (name "/PCA9685_OUT1") (class "Default")
      (node (ref "IC3") (pin "7") (pinfunction "LED1_7") (pintype "passive"))
      (node (ref "R34") (pin "1") (pinfunction "1_1") (pintype "passive"))
    )
    (net (code "47") (name "/PCA9685_OUT2") (class "Default")
      (node (ref "IC3") (pin "8") (pinfunction "LED2_8") (pintype "passive"))
      (node (ref "R33") (pin "1") (pinfunction "1_1") (pintype "passive"))
    )
    (net (code "48") (name "/PCA9685_OUT3") (class "Default")
      (node (ref "IC3") (pin "9") (pinfunction "LED3_9") (pintype "passive"))
      (node (ref "R32") (pin "1") (pinfunction "1_1") (pintype "passive"))
    )
    (net (code "49") (name "/PCA9685_OUT4") (class "Default")
      (node (ref "IC3") (pin "10") (pinfunction "LED4_10") (pintype "passive"))
      (node (ref "R31") (pin "1") (pinfunction "1_1") (pintype "passive"))
    )
    (net (code "50") (name "/PCA9685_OUT5") (class "Default")
      (node (ref "IC3") (pin "11") (pinfunction "LED5_11") (pintype "passive"))
      (node (ref "R30") (pin "1") (pinfunction "1_1") (pintype "passive"))
    )
    (net (code "51") (name "/PCA9685_OUT6") (class "Default")
      (node (ref "IC3") (pin "12") (pinfunction "LED6_12") (pintype "passive"))
      (node (ref "R29") (pin "1") (pinfunction "1_1") (pintype "passive"))
    )
    (net (code "52") (name "/PCA9685_OUT7") (class "Default")
      (node (ref "IC3") (pin "13") (pinfunction "LED7_13") (pintype "passive"))
      (node (ref "R28") (pin "1") (pinfunction "1_1") (pintype "passive"))
    )
    (net (code "53") (name "/PCA9685_OUT8") (class "Default")
      (node (ref "IC3") (pin "15") (pinfunction "LED8_15") (pintype "passive"))
      (node (ref "R70") (pin "1") (pinfunction "1_1") (pintype "passive"))
    )
    (net (code "54") (name "/PCA9685_OUT9") (class "Default")
      (node (ref "IC3") (pin "16") (pinfunction "LED9_16") (pintype "passive"))
      (node (ref "R69") (pin "1") (pinfunction "1_1") (pintype "passive"))
    )
    (net (code "55") (name "/PCA9685_OUT10") (class "Default")
      (node (ref "IC3") (pin "17") (pinfunction "LED10_17") (pintype "passive"))
      (node (ref "R68") (pin "1") (pinfunction "1_1") (pintype "passive"))
    )
    (net (code "56") (name "/PCA9685_OUT11") (class "Default")
      (node (ref "IC3") (pin "18") (pinfunction "LED11_18") (pintype "passive"))
      (node (ref "R67") (pin "1") (pinfunction "1_1") (pintype "passive"))
    )
    (net (code "57") (name "/PCA9685_OUT12") (class "Default")
      (node (ref "IC3") (pin "19") (pinfunction "LED12_19") (pintype "passive"))
      (node (ref "R66") (pin "1") (pinfunction "1_1") (pintype "passive"))
    )
    (net (code "58") (name "/PCA9685_OUT13") (class "Default")
      (node (ref "IC3") (pin "20") (pinfunction "LED13_20") (pintype "passive"))
      (node (ref "R65") (pin "1") (pinfunction "1_1") (pintype "passive"))
    )
    (net (code "59") (name "/PCA9685_OUT14") (class "Default")
      (node (ref "IC3") (pin "21") (pinfunction "LED14_21") (pintype "passive"))
      (node (ref "R64") (pin "1") (pinfunction "1_1") (pintype "passive"))
    )
    (net (code "60") (name "/PCA9685_OUT15") (class "Default")
      (node (ref "IC3") (pin "22") (pinfunction "LED15_22") (pintype "passive"))
      (node (ref "R63") (pin "1") (pinfunction "1_1") (pintype "passive"))
    )
    (net (code "61") (name "/PCA9685_SCL") (class "Default")
      (node (ref "IC3") (pin "26") (pinfunction "SCL_26") (pintype "passive"))
      (node (ref "JP4") (pin "4") (pinfunction "4_4") (pintype "passive"))
    )
    (net (code "62") (name "/PCA9685_SDA") (class "Default")
      (node (ref "IC3") (pin "27") (pinfunction "SDA_27") (pintype "passive"))
      (node (ref "JP4") (pin "3") (pinfunction "3_3") (pintype "passive"))
    )
    (net (code "63") (name "/RELAY1") (class "Default")
      (node (ref "R72") (pin "1") (pinfunction "1_1") (pintype "passive"))
      (node (ref "U2") (pin "32") (pinfunction "PA7/ADC123_IN7/SPI1_MOSI/T8C1N/T3C2/T1C1N_32") (pintype "passive"))
    )
    (net (code "64") (name "/RELAY2") (class "Default")
      (node (ref "R87") (pin "1") (pinfunction "1_1") (pintype "passive"))
      (node (ref "U2") (pin "67") (pinfunction "PA8/T1C1/MCO_67") (pintype "passive"))
    )
    (net (code "65") (name "/RREF") (class "Default")
      (node (ref "IC2") (pin "4") (pinfunction "RREF_4") (pintype "passive"))
      (node (ref "R1") (pin "2") (pinfunction "2_2") (pintype "passive"))
    )
    (net (code "66") (name "/SPI2_MISO") (class "Default")
      (node (ref "U2") (pin "53") (pinfunction "PB14/T1CH2N/SPI2_MISO_53") (pintype "passive"))
    )
    (net (code "67") (name "/SPI2_MOSI") (class "Default")
      (node (ref "U2") (pin "54") (pinfunction "PB15/I2S2_SD/T1CH3N/SPI2_MOSI_54") (pintype "passive"))
    )
    (net (code "68") (name "/SPI2_NSS") (class "Default")
      (node (ref "U2") (pin "51") (pinfunction "PB12/I2S2_WS/T1BKIN/SPI2_NSS/I2C2_SMBA_51") (pintype "passive"))
    )
    (net (code "69") (name "/SPI2_SCLK") (class "Default")
      (node (ref "U2") (pin "52") (pinfunction "PB13/I2S2_CK/T1CH1N/SPI2_SCK_52") (pintype "passive"))
    )
    (net (code "70") (name "/STA_LED") (class "Default")
      (node (ref "LED1") (pin "2") (pinfunction "K_2") (pintype "passive"))
      (node (ref "R71") (pin "2") (pinfunction "2_2") (pintype "passive"))
      (node (ref "U1") (pin "30") (pinfunction "PA9_30") (pintype "bidirectional"))
    )
    (net (code "71") (name "/SWCLK") (class "Default")
      (node (ref "JP17") (pin "2") (pinfunction "2_2") (pintype "passive"))
      (node (ref "JP2") (pin "6") (pinfunction "6_6") (pintype "passive"))
      (node (ref "U1") (pin "37") (pinfunction "PA14/JTCK/SWCLK_37") (pintype "bidirectional"))
    )
    (net (code "72") (name "/SWDIO") (class "Default")
      (node (ref "JP17") (pin "3") (pinfunction "3_3") (pintype "passive"))
      (node (ref "JP2") (pin "5") (pinfunction "5_5") (pintype "passive"))
      (node (ref "U1") (pin "34") (pinfunction "PA13/JTMS/SWDIO_34") (pintype "bidirectional"))
    )
    (net (code "73") (name "/T_JTCK") (class "Default")
      (node (ref "R2") (pin "1") (pinfunction "1_1") (pintype "passive"))
      (node (ref "U1") (pin "26") (pinfunction "PB13_26") (pintype "bidirectional"))
    )
    (net (code "74") (name "/T_JTMS") (class "Default")
      (node (ref "R27") (pin "1") (pinfunction "1_1") (pintype "passive"))
      (node (ref "R3") (pin "1") (pinfunction "1_1") (pintype "passive"))
      (node (ref "U1") (pin "27") (pinfunction "PB14_27") (pintype "bidirectional"))
    )
    (net (code "75") (name "/T_MOSI") (class "Default")
      (node (ref "U1") (pin "28") (pinfunction "PB15_28") (pintype "bidirectional"))
    )
    (net (code "76") (name "/T_SWCLK") (class "Default")
      (node (ref "JP2") (pin "2") (pinfunction "2_2") (pintype "passive"))
      (node (ref "R2") (pin "2") (pinfunction "2_2") (pintype "passive"))
    )
    (net (code "77") (name "/T_SWDIO") (class "Default")
      (node (ref "JP2") (pin "1") (pinfunction "1_1") (pintype "passive"))
      (node (ref "R3") (pin "2") (pinfunction "2_2") (pintype "passive"))
    )
    (net (code "78") (name "/T_SWDIO_IN") (class "Default")
      (node (ref "R27") (pin "2") (pinfunction "2_2") (pintype "passive"))
      (node (ref "U1") (pin "25") (pinfunction "PB12_25") (pintype "bidirectional"))
    )
    (net (code "79") (name "/USART1_RXD") (class "Default")
      (node (ref "JP3") (pin "2") (pinfunction "2_2") (pintype "passive"))
      (node (ref "LED5") (pin "2") (pinfunction "K_2") (pintype "passive"))
      (node (ref "U2") (pin "69") (pinfunction "PA10/T1C3/USART1_Rx_69") (pintype "passive"))
    )
    (net (code "80") (name "/USART1_TXD") (class "Default")
      (node (ref "JP3") (pin "1") (pinfunction "1_1") (pintype "passive"))
      (node (ref "LED4") (pin "2") (pinfunction "K_2") (pintype "passive"))
      (node (ref "U2") (pin "68") (pinfunction "PA9/T1C2/USART1_Tx_68") (pintype "passive"))
    )
    (net (code "81") (name "/USART2_RXD") (class "Default")
      (node (ref "JP3") (pin "6") (pinfunction "6_6") (pintype "passive"))
      (node (ref "LED3") (pin "2") (pinfunction "K_2") (pintype "passive"))
      (node (ref "U2") (pin "26") (pinfunction "PA3/ADC123_IN3/USART2_Rx/T5C4/T2C4_26") (pintype "passive"))
    )
    (net (code "82") (name "/USART2_TXD") (class "Default")
      (node (ref "JP3") (pin "5") (pinfunction "5_5") (pintype "passive"))
      (node (ref "LED2") (pin "2") (pinfunction "K_2") (pintype "passive"))
      (node (ref "U2") (pin "25") (pinfunction "PA2/ADC123_IN2/USART2_Tx/T5C3/T2C3_25") (pintype "passive"))
    )
    (net (code "83") (name "/USART3_RXD") (class "Default")
      (node (ref "JP1") (pin "1") (pinfunction "1_1") (pintype "passive"))
      (node (ref "U2") (pin "56") (pinfunction "PD9/USART3_Rx/FSMC_D14_56") (pintype "passive"))
    )
    (net (code "84") (name "/USART3_TXD") (class "Default")
      (node (ref "JP1") (pin "2") (pinfunction "2_2") (pintype "passive"))
      (node (ref "U2") (pin "55") (pinfunction "PD8/USART3_Tx/FSMC_D13_55") (pintype "passive"))
    )
    (net (code "85") (name "/USART4_RXD") (class "Default")
      (node (ref "JP1") (pin "5") (pinfunction "5_5") (pintype "passive"))
      (node (ref "U2") (pin "79") (pinfunction "PC11/UART4_Rx/SDIO_D3_79") (pintype "passive"))
    )
    (net (code "86") (name "/USART4_TXD") (class "Default")
      (node (ref "JP1") (pin "6") (pinfunction "6_6") (pintype "passive"))
      (node (ref "U2") (pin "78") (pinfunction "PC10/UART4_Tx/SDIO_D2_78") (pintype "passive"))
    )
    (net (code "87") (name "/USB0_N") (class "Default")
      (node (ref "IC2") (pin "25") (pinfunction "DM0_25") (pintype "passive"))
      (node (ref "USB1") (pin "2") (pinfunction "D-_2") (pintype "passive"))
    )
    (net (code "88") (name "/USB0_P") (class "Default")
      (node (ref "IC2") (pin "26") (pinfunction "DP0_26") (pintype "passive"))
      (node (ref "USB1") (pin "3") (pinfunction "D+_3") (pintype "passive"))
    )
    (net (code "89") (name "/USB1_N") (class "Default")
      (node (ref "IC2") (pin "27") (pinfunction "DM1_27") (pintype "passive"))
      (node (ref "R8") (pin "1") (pinfunction "1_1") (pintype "passive"))
    )
    (net (code "90") (name "/USB1_P") (class "Default")
      (node (ref "IC2") (pin "28") (pinfunction "DP1_28") (pintype "passive"))
      (node (ref "R7") (pin "1") (pinfunction "1_1") (pintype "passive"))
    )
    (net (code "91") (name "/USB2_N") (class "Default")
      (node (ref "IC1") (pin "6") (pinfunction "UD-_6") (pintype "passive"))
      (node (ref "IC2") (pin "2") (pinfunction "DM2_2") (pintype "passive"))
    )
    (net (code "92") (name "/USB2_P") (class "Default")
      (node (ref "IC1") (pin "5") (pinfunction "UD+_5") (pintype "passive"))
      (node (ref "IC2") (pin "3") (pinfunction "DP2_3") (pintype "passive"))
    )
    (net (code "93") (name "/USB3_N") (class "Default")
      (node (ref "IC2") (pin "8") (pinfunction "DM3_8") (pintype "passive"))
      (node (ref "USB3") (pin "2") (pinfunction "D-_2") (pintype "passive"))
    )
    (net (code "94") (name "/USB3_P") (class "Default")
      (node (ref "IC2") (pin "9") (pinfunction "DP3_9") (pintype "passive"))
      (node (ref "USB3") (pin "3") (pinfunction "D+_3") (pintype "passive"))
    )
    (net (code "95") (name "/USB4_N") (class "Default")
      (node (ref "IC2") (pin "11") (pinfunction "DM4_11") (pintype "passive"))
      (node (ref "USB2") (pin "2") (pinfunction "D-_2") (pintype "passive"))
    )
    (net (code "96") (name "/USB4_P") (class "Default")
      (node (ref "IC2") (pin "12") (pinfunction "DP4_12") (pintype "passive"))
      (node (ref "USB2") (pin "3") (pinfunction "D+_3") (pintype "passive"))
    )
    (net (code "97") (name "/WORK_LED") (class "Default")
      (node (ref "LED9") (pin "2") (pinfunction "K_2") (pintype "passive"))
      (node (ref "U2") (pin "70") (pinfunction "PA11/CAN_Rx/T1C4/USBDM_70") (pintype "passive"))
    )
    (net (code "98") (name "BACKUP_5V") (class "Default")
      (node (ref "M1") (pin "8") (pinfunction "VOUT_8") (pintype "passive"))
      (node (ref "VD1") (pin "1") (pinfunction "A_1") (pintype "passive"))
      (node (ref "VD2") (pin "1") (pinfunction "A_1") (pintype "passive"))
      (node (ref "VD3") (pin "1") (pinfunction "A_1") (pintype "passive"))
    )
    (net (code "99") (name "BOARD_5V") (class "Default")
      (node (ref "C13") (pin "2") (pinfunction "2_2") (pintype "passive"))
      (node (ref "C14") (pin "2") (pinfunction "2_2") (pintype "passive"))
      (node (ref "C15") (pin "2") (pinfunction "2_2") (pintype "passive"))
      (node (ref "C16") (pin "2") (pinfunction "2_2") (pintype "passive"))
      (node (ref "C17") (pin "2") (pinfunction "2_2") (pintype "passive"))
      (node (ref "C18") (pin "2") (pinfunction "2_2") (pintype "passive"))
      (node (ref "C19") (pin "2") (pinfunction "2_2") (pintype "passive"))
      (node (ref "C20") (pin "2") (pinfunction "2_2") (pintype "passive"))
      (node (ref "C21") (pin "2") (pinfunction "2_2") (pintype "passive"))
      (node (ref "C22") (pin "2") (pinfunction "2_2") (pintype "passive"))
      (node (ref "C23") (pin "2") (pinfunction "2_2") (pintype "passive"))
      (node (ref "C24") (pin "2") (pinfunction "2_2") (pintype "passive"))
      (node (ref "C25") (pin "2") (pinfunction "2_2") (pintype "passive"))
      (node (ref "C26") (pin "2") (pinfunction "2_2") (pintype "passive"))
      (node (ref "C27") (pin "2") (pinfunction "2_2") (pintype "passive"))
      (node (ref "C28") (pin "2") (pinfunction "2_2") (pintype "passive"))
      (node (ref "C29") (pin "2") (pinfunction "2_2") (pintype "passive"))
      (node (ref "C30") (pin "2") (pinfunction "2_2") (pintype "passive"))
      (node (ref "C31") (pin "2") (pinfunction "2_2") (pintype "passive"))
      (node (ref "C32") (pin "2") (pinfunction "2_2") (pintype "passive"))
      (node (ref "C33") (pin "2") (pinfunction "2_2") (pintype "passive"))
      (node (ref "C34") (pin "2") (pinfunction "2_2") (pintype "passive"))
      (node (ref "C35") (pin "2") (pinfunction "2_2") (pintype "passive"))
      (node (ref "C36") (pin "2") (pinfunction "2_2") (pintype "passive"))
      (node (ref "C37") (pin "2") (pinfunction "2_2") (pintype "passive"))
      (node (ref "C38") (pin "2") (pinfunction "2_2") (pintype "passive"))
      (node (ref "C39") (pin "2") (pinfunction "2_2") (pintype "passive"))
      (node (ref "C40") (pin "2") (pinfunction "2_2") (pintype "passive"))
      (node (ref "C41") (pin "2") (pinfunction "2_2") (pintype "passive"))
      (node (ref "C42") (pin "2") (pinfunction "2_2") (pintype "passive"))
      (node (ref "C43") (pin "2") (pinfunction "2_2") (pintype "passive"))
      (node (ref "C44") (pin "2") (pinfunction "2_2") (pintype "passive"))
      (node (ref "C45") (pin "2") (pinfunction "2_2") (pintype "passive"))
      (node (ref "C46") (pin "2") (pinfunction "2_2") (pintype "passive"))
      (node (ref "C47") (pin "2") (pinfunction "2_2") (pintype "passive"))
      (node (ref "C48") (pin "2") (pinfunction "2_2") (pintype "passive"))
      (node (ref "E3") (pin "1") (pinfunction "A_1") (pintype "passive"))
      (node (ref "E4") (pin "1") (pinfunction "A_1") (pintype "passive"))
      (node (ref "IC1") (pin "16") (pinfunction "Vcc_16") (pintype "passive"))
      (node (ref "IC10") (pin "8") (pinfunction "VCC_8") (pintype "passive"))
      (node (ref "IC11") (pin "8") (pinfunction "VCC_8") (pintype "passive"))
      (node (ref "IC12") (pin "8") (pinfunction "VCC_8") (pintype "passive"))
      (node (ref "IC13") (pin "8") (pinfunction "VCC_8") (pintype "passive"))
      (node (ref "IC2") (pin "23") (pinfunction "V5_23") (pintype "passive"))
      (node (ref "IC3") (pin "28") (pinfunction "VDD_28") (pintype "passive"))
      (node (ref "IC4") (pin "8") (pinfunction "VCC_8") (pintype "passive"))
      (node (ref "IC5") (pin "8") (pinfunction "VCC_8") (pintype "passive"))
      (node (ref "IC6") (pin "8") (pinfunction "VCC_8") (pintype "passive"))
      (node (ref "IC7") (pin "8") (pinfunction "VCC_8") (pintype "passive"))
      (node (ref "IC8") (pin "8") (pinfunction "VCC_8") (pintype "passive"))
      (node (ref "IC9") (pin "8") (pinfunction "VCC_8") (pintype "passive"))
      (node (ref "JK1") (pin "2") (pinfunction "2_2") (pintype "passive"))
      (node (ref "JK2") (pin "2") (pinfunction "2_2") (pintype "passive"))
      (node (ref "JP18") (pin "2") (pinfunction "2_2") (pintype "passive"))
      (node (ref "JP18") (pin "4") (pinfunction "4_4") (pintype "passive"))
      (node (ref "JP18") (pin "6") (pinfunction "6_6") (pintype "passive"))
      (node (ref "JP18") (pin "8") (pinfunction "8_8") (pintype "passive"))
      (node (ref "JP6") (pin "1") (pinfunction "1_1") (pintype "passive"))
      (node (ref "JP6") (pin "2") (pinfunction "2_2") (pintype "passive"))
      (node (ref "M5") (pin "8") (pinfunction "VOUT_8") (pintype "passive"))
      (node (ref "R19") (pin "2") (pinfunction "2_2") (pintype "passive"))
      (node (ref "R20") (pin "2") (pinfunction "2_2") (pintype "passive"))
      (node (ref "R21") (pin "2") (pinfunction "2_2") (pintype "passive"))
      (node (ref "R22") (pin "2") (pinfunction "2_2") (pintype "passive"))
      (node (ref "R45") (pin "2") (pinfunction "2_2") (pintype "passive"))
      (node (ref "R46") (pin "2") (pinfunction "2_2") (pintype "passive"))
      (node (ref "R47") (pin "2") (pinfunction "2_2") (pintype "passive"))
      (node (ref "R48") (pin "2") (pinfunction "2_2") (pintype "passive"))
      (node (ref "R49") (pin "2") (pinfunction "2_2") (pintype "passive"))
      (node (ref "R50") (pin "2") (pinfunction "2_2") (pintype "passive"))
      (node (ref "R55") (pin "1") (pinfunction "1_1") (pintype "passive"))
      (node (ref "R56") (pin "1") (pinfunction "1_1") (pintype "passive"))
      (node (ref "R57") (pin "1") (pinfunction "1_1") (pintype "passive"))
      (node (ref "R58") (pin "1") (pinfunction "1_1") (pintype "passive"))
      (node (ref "R59") (pin "1") (pinfunction "1_1") (pintype "passive"))
      (node (ref "R60") (pin "1") (pinfunction "1_1") (pintype "passive"))
      (node (ref "R61") (pin "1") (pinfunction "1_1") (pintype "passive"))
      (node (ref "R62") (pin "1") (pinfunction "1_1") (pintype "passive"))
      (node (ref "R77") (pin "2") (pinfunction "2_2") (pintype "passive"))
      (node (ref "R79") (pin "1") (pinfunction "1_1") (pintype "passive"))
      (node (ref "R80") (pin "1") (pinfunction "1_1") (pintype "passive"))
      (node (ref "R81") (pin "1") (pinfunction "1_1") (pintype "passive"))
      (node (ref "R82") (pin "1") (pinfunction "1_1") (pintype "passive"))
      (node (ref "R83") (pin "1") (pinfunction "1_1") (pintype "passive"))
      (node (ref "R84") (pin "1") (pinfunction "1_1") (pintype "passive"))
      (node (ref "R85") (pin "1") (pinfunction "1_1") (pintype "passive"))
      (node (ref "R86") (pin "1") (pinfunction "1_1") (pintype "passive"))
      (node (ref "R89") (pin "1") (pinfunction "1_1") (pintype "passive"))
      (node (ref "USB2") (pin "1") (pinfunction "VCC_1") (pintype "passive"))
      (node (ref "USB3") (pin "1") (pinfunction "VCC_1") (pintype "passive"))
      (node (ref "V1") (pin "3") (pinfunction "Vin_3") (pintype "passive"))
      (node (ref "V2") (pin "3") (pinfunction "Vin_3") (pintype "passive"))
      (node (ref "V3") (pin "3") (pinfunction "Vin_3") (pintype "passive"))
      (node (ref "VD4") (pin "2") (pinfunction "K_2") (pintype "passive"))
      (node (ref "VD5") (pin "2") (pinfunction "K_2") (pintype "passive"))
    )
    (net (code "100") (name "EXT_3V") (class "Default")
      (node (ref "JP19") (pin "2") (pinfunction "2_2") (pintype "passive"))
      (node (ref "JP19") (pin "4") (pinfunction "4_4") (pintype "passive"))
      (node (ref "JP19") (pin "6") (pinfunction "6_6") (pintype "passive"))
      (node (ref "JP19") (pin "8") (pinfunction "8_8") (pintype "passive"))
      (node (ref "JP7") (pin "1") (pinfunction "1_1") (pintype "passive"))
      (node (ref "JP7") (pin "2") (pinfunction "2_2") (pintype "passive"))
      (node (ref "V1") (pin "2") (pinfunction "Vout_2") (pintype "passive"))
    )
    (net (code "101") (name "GND") (class "Default")
      (node (ref "C1") (pin "1") (pinfunction "1_1") (pintype "passive"))
      (node (ref "C10") (pin "1") (pinfunction "1_1") (pintype "passive"))
      (node (ref "C11") (pin "1") (pinfunction "1_1") (pintype "passive"))
      (node (ref "C12") (pin "1") (pinfunction "1_1") (pintype "passive"))
      (node (ref "C13") (pin "1") (pinfunction "1_1") (pintype "passive"))
      (node (ref "C14") (pin "1") (pinfunction "1_1") (pintype "passive"))
      (node (ref "C15") (pin "1") (pinfunction "1_1") (pintype "passive"))
      (node (ref "C16") (pin "1") (pinfunction "1_1") (pintype "passive"))
      (node (ref "C17") (pin "1") (pinfunction "1_1") (pintype "passive"))
      (node (ref "C18") (pin "1") (pinfunction "1_1") (pintype "passive"))
      (node (ref "C19") (pin "1") (pinfunction "1_1") (pintype "passive"))
      (node (ref "C2") (pin "1") (pinfunction "1_1") (pintype "passive"))
      (node (ref "C20") (pin "1") (pinfunction "1_1") (pintype "passive"))
      (node (ref "C21") (pin "1") (pinfunction "1_1") (pintype "passive"))
      (node (ref "C22") (pin "1") (pinfunction "1_1") (pintype "passive"))
      (node (ref "C23") (pin "1") (pinfunction "1_1") (pintype "passive"))
      (node (ref "C24") (pin "1") (pinfunction "1_1") (pintype "passive"))
      (node (ref "C25") (pin "1") (pinfunction "1_1") (pintype "passive"))
      (node (ref "C26") (pin "1") (pinfunction "1_1") (pintype "passive"))
      (node (ref "C27") (pin "1") (pinfunction "1_1") (pintype "passive"))
      (node (ref "C28") (pin "1") (pinfunction "1_1") (pintype "passive"))
      (node (ref "C29") (pin "1") (pinfunction "1_1") (pintype "passive"))
      (node (ref "C3") (pin "1") (pinfunction "1_1") (pintype "passive"))
      (node (ref "C30") (pin "1") (pinfunction "1_1") (pintype "passive"))
      (node (ref "C31") (pin "1") (pinfunction "1_1") (pintype "passive"))
      (node (ref "C32") (pin "1") (pinfunction "1_1") (pintype "passive"))
      (node (ref "C33") (pin "1") (pinfunction "1_1") (pintype "passive"))
      (node (ref "C34") (pin "1") (pinfunction "1_1") (pintype "passive"))
      (node (ref "C35") (pin "1") (pinfunction "1_1") (pintype "passive"))
      (node (ref "C36") (pin "1") (pinfunction "1_1") (pintype "passive"))
      (node (ref "C37") (pin "1") (pinfunction "1_1") (pintype "passive"))
      (node (ref "C38") (pin "1") (pinfunction "1_1") (pintype "passive"))
      (node (ref "C39") (pin "1") (pinfunction "1_1") (pintype "passive"))
      (node (ref "C4") (pin "1") (pinfunction "1_1") (pintype "passive"))
      (node (ref "C40") (pin "1") (pinfunction "1_1") (pintype "passive"))
      (node (ref "C41") (pin "1") (pinfunction "1_1") (pintype "passive"))
      (node (ref "C42") (pin "1") (pinfunction "1_1") (pintype "passive"))
      (node (ref "C43") (pin "1") (pinfunction "1_1") (pintype "passive"))
      (node (ref "C44") (pin "1") (pinfunction "1_1") (pintype "passive"))
      (node (ref "C45") (pin "1") (pinfunction "1_1") (pintype "passive"))
      (node (ref "C46") (pin "1") (pinfunction "1_1") (pintype "passive"))
      (node (ref "C47") (pin "1") (pinfunction "1_1") (pintype "passive"))
      (node (ref "C48") (pin "1") (pinfunction "1_1") (pintype "passive"))
      (node (ref "C49") (pin "1") (pinfunction "1_1") (pintype "passive"))
      (node (ref "C5") (pin "1") (pinfunction "1_1") (pintype "passive"))
      (node (ref "C50") (pin "1") (pinfunction "1_1") (pintype "passive"))
      (node (ref "C51") (pin "1") (pinfunction "1_1") (pintype "passive"))
      (node (ref "C6") (pin "1") (pinfunction "1_1") (pintype "passive"))
      (node (ref "C7") (pin "1") (pinfunction "1_1") (pintype "passive"))
      (node (ref "C8") (pin "1") (pinfunction "1_1") (pintype "passive"))
      (node (ref "C9") (pin "1") (pinfunction "1_1") (pintype "passive"))
      (node (ref "E1") (pin "2") (pinfunction "K_2") (pintype "passive"))
      (node (ref "E10") (pin "2") (pinfunction "K_2") (pintype "passive"))
      (node (ref "E11") (pin "2") (pinfunction "K_2") (pintype "passive"))
      (node (ref "E2") (pin "2") (pinfunction "K_2") (pintype "passive"))
      (node (ref "E3") (pin "2") (pinfunction "K_2") (pintype "passive"))
      (node (ref "E4") (pin "2") (pinfunction "K_2") (pintype "passive"))
      (node (ref "E5") (pin "2") (pinfunction "K_2") (pintype "passive"))
      (node (ref "E6") (pin "2") (pinfunction "K_2") (pintype "passive"))
      (node (ref "E7") (pin "2") (pinfunction "K_2") (pintype "passive"))
      (node (ref "E8") (pin "2") (pinfunction "K_2") (pintype "passive"))
      (node (ref "E9") (pin "2") (pinfunction "K_2") (pintype "passive"))
      (node (ref "IC1") (pin "1") (pinfunction "GND_1") (pintype "passive"))
      (node (ref "IC10") (pin "5") (pinfunction "GND_5") (pintype "passive"))
      (node (ref "IC11") (pin "5") (pinfunction "GND_5") (pintype "passive"))
      (node (ref "IC12") (pin "5") (pinfunction "GND_5") (pintype "passive"))
      (node (ref "IC13") (pin "5") (pinfunction "GND_5") (pintype "passive"))
      (node (ref "IC2") (pin "15") (pinfunction "GND_15") (pintype "passive"))
      (node (ref "IC3") (pin "14") (pinfunction "VSS_14") (pintype "passive"))
      (node (ref "IC4") (pin "5") (pinfunction "GND_5") (pintype "passive"))
      (node (ref "IC5") (pin "5") (pinfunction "GND_5") (pintype "passive"))
      (node (ref "IC6") (pin "5") (pinfunction "GND_5") (pintype "passive"))
      (node (ref "IC7") (pin "5") (pinfunction "GND_5") (pintype "passive"))
      (node (ref "IC8") (pin "5") (pinfunction "GND_5") (pintype "passive"))
      (node (ref "IC9") (pin "5") (pinfunction "GND_5") (pintype "passive"))
      (node (ref "JP10") (pin "1") (pinfunction "1_1") (pintype "passive"))
      (node (ref "JP10") (pin "10") (pinfunction "10_10") (pintype "passive"))
      (node (ref "JP10") (pin "11") (pinfunction "11_11") (pintype "passive"))
      (node (ref "JP10") (pin "12") (pinfunction "12_12") (pintype "passive"))
      (node (ref "JP10") (pin "13") (pinfunction "13_13") (pintype "passive"))
      (node (ref "JP10") (pin "14") (pinfunction "14_14") (pintype "passive"))
      (node (ref "JP10") (pin "15") (pinfunction "15_15") (pintype "passive"))
      (node (ref "JP10") (pin "16") (pinfunction "16_16") (pintype "passive"))
      (node (ref "JP10") (pin "2") (pinfunction "2_2") (pintype "passive"))
      (node (ref "JP10") (pin "3") (pinfunction "3_3") (pintype "passive"))
      (node (ref "JP10") (pin "4") (pinfunction "4_4") (pintype "passive"))
      (node (ref "JP10") (pin "5") (pinfunction "5_5") (pintype "passive"))
      (node (ref "JP10") (pin "6") (pinfunction "6_6") (pintype "passive"))
      (node (ref "JP10") (pin "7") (pinfunction "7_7") (pintype "passive"))
      (node (ref "JP10") (pin "8") (pinfunction "8_8") (pintype "passive"))
      (node (ref "JP10") (pin "9") (pinfunction "9_9") (pintype "passive"))
      (node (ref "JP11") (pin "1") (pinfunction "1_1") (pintype "passive"))
      (node (ref "JP12") (pin "2") (pinfunction "2_2") (pintype "passive"))
      (node (ref "JP13") (pin "2") (pinfunction "2_2") (pintype "passive"))
      (node (ref "JP13") (pin "4") (pinfunction "4_4") (pintype "passive"))
      (node (ref "JP13") (pin "6") (pinfunction "6_6") (pintype "passive"))
      (node (ref "JP13") (pin "8") (pinfunction "8_8") (pintype "passive"))
      (node (ref "JP14") (pin "2") (pinfunction "2_2") (pintype "passive"))
      (node (ref "JP14") (pin "4") (pinfunction "4_4") (pintype "passive"))
      (node (ref "JP14") (pin "6") (pinfunction "6_6") (pintype "passive"))
      (node (ref "JP14") (pin "8") (pinfunction "8_8") (pintype "passive"))
      (node (ref "JP15") (pin "2") (pinfunction "2_2") (pintype "passive"))
      (node (ref "JP15") (pin "4") (pinfunction "4_4") (pintype "passive"))
      (node (ref "JP15") (pin "6") (pinfunction "6_6") (pintype "passive"))
      (node (ref "JP15") (pin "8") (pinfunction "8_8") (pintype "passive"))
      (node (ref "JP17") (pin "1") (pinfunction "1_1") (pintype "passive"))
      (node (ref "JP18") (pin "1") (pinfunction "1_1") (pintype "passive"))
      (node (ref "JP18") (pin "3") (pinfunction "3_3") (pintype "passive"))
      (node (ref "JP18") (pin "5") (pinfunction "5_5") (pintype "passive"))
      (node (ref "JP18") (pin "7") (pinfunction "7_7") (pintype "passive"))
      (node (ref "JP19") (pin "1") (pinfunction "1_1") (pintype "passive"))
      (node (ref "JP19") (pin "3") (pinfunction "3_3") (pintype "passive"))
      (node (ref "JP19") (pin "5") (pinfunction "5_5") (pintype "passive"))
      (node (ref "JP19") (pin "7") (pinfunction "7_7") (pintype "passive"))
      (node (ref "JP20") (pin "1") (pinfunction "1_1") (pintype "passive"))
      (node (ref "JP20") (pin "3") (pinfunction "3_3") (pintype "passive"))
      (node (ref "JP20") (pin "5") (pinfunction "5_5") (pintype "passive"))
      (node (ref "JP20") (pin "7") (pinfunction "7_7") (pintype "passive"))
      (node (ref "JP21") (pin "2") (pinfunction "2_2") (pintype "passive"))
      (node (ref "JP6") (pin "7") (pinfunction "7_7") (pintype "passive"))
      (node (ref "JP6") (pin "8") (pinfunction "8_8") (pintype "passive"))
      (node (ref "JP7") (pin "7") (pinfunction "7_7") (pintype "passive"))
      (node (ref "JP7") (pin "8") (pinfunction "8_8") (pintype "passive"))
      (node (ref "LED10") (pin "2") (pinfunction "K_2") (pintype "passive"))
      (node (ref "LED11") (pin "2") (pinfunction "K_2") (pintype "passive"))
      (node (ref "LED12") (pin "2") (pinfunction "K_2") (pintype "passive"))
      (node (ref "LED13") (pin "2") (pinfunction "K_2") (pintype "passive"))
      (node (ref "LED14") (pin "2") (pinfunction "K_2") (pintype "passive"))
      (node (ref "LED15") (pin "2") (pinfunction "K_2") (pintype "passive"))
      (node (ref "LED16") (pin "2") (pinfunction "K_2") (pintype "passive"))
      (node (ref "M1") (pin "2") (pinfunction "GND_2") (pintype "passive"))
      (node (ref "M1") (pin "7") (pinfunction "GND_7") (pintype "passive"))
      (node (ref "M2") (pin "2") (pinfunction "GND_2") (pintype "passive"))
      (node (ref "M2") (pin "7") (pinfunction "GND_7") (pintype "passive"))
      (node (ref "M3") (pin "2") (pinfunction "GND_2") (pintype "passive"))
      (node (ref "M3") (pin "7") (pinfunction "GND_7") (pintype "passive"))
      (node (ref "M4") (pin "2") (pinfunction "GND_2") (pintype "passive"))
      (node (ref "M4") (pin "7") (pinfunction "GND_7") (pintype "passive"))
      (node (ref "M5") (pin "2") (pinfunction "GND_2") (pintype "passive"))
      (node (ref "M5") (pin "7") (pinfunction "GND_7") (pintype "passive"))
      (node (ref "M6") (pin "2") (pinfunction "GND_2") (pintype "passive"))
      (node (ref "M6") (pin "7") (pinfunction "GND_7") (pintype "passive"))
      (node (ref "Q1") (pin "2") (pinfunction "E_2") (pintype "passive"))
      (node (ref "Q2") (pin "2") (pinfunction "E_2") (pintype "passive"))
      (node (ref "R1") (pin "1") (pinfunction "1_1") (pintype "passive"))
      (node (ref "R10") (pin "3") (pinfunction "3_3") (pintype "passive"))
      (node (ref "R11") (pin "1") (pinfunction "1_1") (pintype "passive"))
      (node (ref "R12") (pin "1") (pinfunction "1_1") (pintype "passive"))
      (node (ref "R13") (pin "1") (pinfunction "1_1") (pintype "passive"))
      (node (ref "R14") (pin "1") (pinfunction "1_1") (pintype "passive"))
      (node (ref "R15") (pin "1") (pinfunction "1_1") (pintype "passive"))
      (node (ref "R17") (pin "2") (pinfunction "2_2") (pintype "passive"))
      (node (ref "R18") (pin "2") (pinfunction "2_2") (pintype "passive"))
      (node (ref "R23") (pin "2") (pinfunction "2_2") (pintype "passive"))
      (node (ref "R5") (pin "1") (pinfunction "1_1") (pintype "passive"))
      (node (ref "R53") (pin "2") (pinfunction "2_2") (pintype "passive"))
      (node (ref "R54") (pin "2") (pinfunction "2_2") (pintype "passive"))
      (node (ref "R88") (pin "2") (pinfunction "2_2") (pintype "passive"))
      (node (ref "R9") (pin "1") (pinfunction "1_1") (pintype "passive"))
      (node (ref "R90") (pin "1") (pinfunction "1_1") (pintype "passive"))
      (node (ref "RP1") (pin "3") (pinfunction "3_3") (pintype "passive"))
      (node (ref "RP2") (pin "3") (pinfunction "3_3") (pintype "passive"))
      (node (ref "RP3") (pin "3") (pinfunction "3_3") (pintype "passive"))
      (node (ref "RP4") (pin "3") (pinfunction "3_3") (pintype "passive"))
      (node (ref "RP5") (pin "3") (pinfunction "3_3") (pintype "passive"))
      (node (ref "U1") (pin "20") (pinfunction "PB2/BOOT1_20") (pintype "bidirectional"))
      (node (ref "U1") (pin "23") (pinfunction "VSS_1_23") (pintype "power_in"))
      (node (ref "U1") (pin "35") (pinfunction "VSS_2_35") (pintype "power_in"))
      (node (ref "U1") (pin "47") (pinfunction "VSS_3_47") (pintype "power_in"))
      (node (ref "U1") (pin "8") (pinfunction "VSSA_8") (pintype "power_in"))
      (node (ref "U2") (pin "10") (pinfunction "VSS_5_10") (pintype "passive"))
      (node (ref "U2") (pin "19") (pinfunction "VSSA_19") (pintype "passive"))
      (node (ref "U2") (pin "20") (pinfunction "VREF-_20") (pintype "passive"))
      (node (ref "U2") (pin "27") (pinfunction "VSS_4_27") (pintype "passive"))
      (node (ref "U2") (pin "37") (pinfunction "PB2/BOOT1_37") (pintype "passive"))
      (node (ref "U2") (pin "49") (pinfunction "VSS_1_49") (pintype "passive"))
      (node (ref "U2") (pin "74") (pinfunction "VSS_2_74") (pintype "passive"))
      (node (ref "U2") (pin "99") (pinfunction "VSS_3_99") (pintype "passive"))
      (node (ref "USB1") (pin "5") (pinfunction "GND_5") (pintype "passive"))
      (node (ref "USB2") (pin "4") (pinfunction "GND_4") (pintype "passive"))
      (node (ref "USB3") (pin "4") (pinfunction "GND_4") (pintype "passive"))
      (node (ref "V1") (pin "1") (pinfunction "GND_1") (pintype "passive"))
      (node (ref "V2") (pin "1") (pinfunction "GND_1") (pintype "passive"))
      (node (ref "V3") (pin "1") (pinfunction "GND_1") (pintype "passive"))
    )
    (net (code "102") (name "MAIN_12V") (class "Default")
      (node (ref "E11") (pin "1") (pinfunction "A_1") (pintype "passive"))
      (node (ref "JK1") (pin "3") (pinfunction "3_3") (pintype "passive"))
      (node (ref "JK2") (pin "3") (pinfunction "3_3") (pintype "passive"))
      (node (ref "JP11") (pin "2") (pinfunction "2_2") (pintype "passive"))
      (node (ref "M1") (pin "1") (pinfunction "VIN_1") (pintype "passive"))
      (node (ref "M2") (pin "1") (pinfunction "VIN_1") (pintype "passive"))
      (node (ref "M3") (pin "1") (pinfunction "VIN_1") (pintype "passive"))
      (node (ref "M4") (pin "1") (pinfunction "VIN_1") (pintype "passive"))
      (node (ref "M5") (pin "1") (pinfunction "VIN_1") (pintype "passive"))
      (node (ref "M6") (pin "1") (pinfunction "VIN_1") (pintype "passive"))
      (node (ref "R73") (pin "2") (pinfunction "2_2") (pintype "passive"))
    )
    (net (code "103") (name "MCU_3V") (class "Default")
      (node (ref "IC10") (pin "1") (pinfunction "IN+_1") (pintype "passive"))
      (node (ref "IC10") (pin "4") (pinfunction "IN+_4") (pintype "passive"))
      (node (ref "IC11") (pin "1") (pinfunction "IN+_1") (pintype "passive"))
      (node (ref "IC11") (pin "4") (pinfunction "IN+_4") (pintype "passive"))
      (node (ref "IC4") (pin "1") (pinfunction "IN+_1") (pintype "passive"))
      (node (ref "IC4") (pin "4") (pinfunction "IN+_4") (pintype "passive"))
      (node (ref "IC5") (pin "1") (pinfunction "IN+_1") (pintype "passive"))
      (node (ref "IC5") (pin "4") (pinfunction "IN+_4") (pintype "passive"))
      (node (ref "IC6") (pin "1") (pinfunction "IN+_1") (pintype "passive"))
      (node (ref "IC6") (pin "4") (pinfunction "IN+_4") (pintype "passive"))
      (node (ref "IC7") (pin "1") (pinfunction "IN+_1") (pintype "passive"))
      (node (ref "IC7") (pin "4") (pinfunction "IN+_4") (pintype "passive"))
      (node (ref "IC8") (pin "1") (pinfunction "IN+_1") (pintype "passive"))
      (node (ref "IC8") (pin "4") (pinfunction "IN+_4") (pintype "passive"))
      (node (ref "IC9") (pin "1") (pinfunction "IN+_1") (pintype "passive"))
      (node (ref "IC9") (pin "4") (pinfunction "IN+_4") (pintype "passive"))
      (node (ref "R24") (pin "2") (pinfunction "2_2") (pintype "passive"))
      (node (ref "R51") (pin "2") (pinfunction "2_2") (pintype "passive"))
      (node (ref "R52") (pin "2") (pinfunction "2_2") (pintype "passive"))
      (node (ref "U2") (pin "100") (pinfunction "VDD_3_100") (pintype "passive"))
      (node (ref "U2") (pin "11") (pinfunction "VDD_5_11") (pintype "passive"))
      (node (ref "U2") (pin "21") (pinfunction "VREF+_21") (pintype "passive"))
      (node (ref "U2") (pin "22") (pinfunction "VDDA_22") (pintype "passive"))
      (node (ref "U2") (pin "28") (pinfunction "VDD_4_28") (pintype "passive"))
      (node (ref "U2") (pin "50") (pinfunction "VDD_1_50") (pintype "passive"))
      (node (ref "U2") (pin "75") (pinfunction "VDD_2_75") (pintype "passive"))
      (node (ref "V2") (pin "2") (pinfunction "Vout_2") (pintype "passive"))
    )
    (net (code "104") (name "Net-(IC1-XI)") (class "Default")
      (node (ref "C4") (pin "2") (pinfunction "2_2") (pintype "passive"))
      (node (ref "IC1") (pin "7") (pinfunction "XI_7") (pintype "passive"))
      (node (ref "X2") (pin "2") (pinfunction "2_2") (pintype "passive"))
    )
    (net (code "105") (name "Net-(IC1-XO)") (class "Default")
      (node (ref "C3") (pin "2") (pinfunction "2_2") (pintype "passive"))
      (node (ref "IC1") (pin "8") (pinfunction "XO_8") (pintype "passive"))
      (node (ref "X2") (pin "1") (pinfunction "1_1") (pintype "passive"))
    )
    (net (code "106") (name "Net-(IC2-XTAL1)") (class "Default")
      (node (ref "C6") (pin "2") (pinfunction "2_2") (pintype "passive"))
      (node (ref "IC2") (pin "6") (pinfunction "XTAL1_6") (pintype "passive"))
      (node (ref "X3") (pin "1") (pinfunction "1_1") (pintype "passive"))
    )
    (net (code "107") (name "Net-(IC2-XTAL2)") (class "Default")
      (node (ref "C5") (pin "2") (pinfunction "2_2") (pintype "passive"))
      (node (ref "IC2") (pin "7") (pinfunction "XTAL2_7") (pintype "passive"))
      (node (ref "X3") (pin "2") (pinfunction "2_2") (pintype "passive"))
    )
    (net (code "108") (name "Net-(IC2-~{RESET})") (class "Default")
      (node (ref "C7") (pin "2") (pinfunction "2_2") (pintype "passive"))
      (node (ref "IC2") (pin "13") (pinfunction "~{RESET}_13") (pintype "passive"))
      (node (ref "R4") (pin "2") (pinfunction "2_2") (pintype "passive"))
    )
    (net (code "109") (name "Net-(IC3-A0)") (class "Default")
      (node (ref "IC3") (pin "1") (pinfunction "A0_1") (pintype "passive"))
      (node (ref "R15") (pin "2") (pinfunction "2_2") (pintype "passive"))
    )
    (net (code "110") (name "Net-(IC3-A1)") (class "Default")
      (node (ref "IC3") (pin "2") (pinfunction "A1_2") (pintype "passive"))
      (node (ref "R14") (pin "2") (pinfunction "2_2") (pintype "passive"))
    )
    (net (code "111") (name "Net-(IC3-A2)") (class "Default")
      (node (ref "IC3") (pin "3") (pinfunction "A2_3") (pintype "passive"))
      (node (ref "R13") (pin "2") (pinfunction "2_2") (pintype "passive"))
    )
    (net (code "112") (name "Net-(IC3-A3)") (class "Default")
      (node (ref "IC3") (pin "4") (pinfunction "A3_4") (pintype "passive"))
      (node (ref "R12") (pin "2") (pinfunction "2_2") (pintype "passive"))
    )
    (net (code "113") (name "Net-(IC3-A4)") (class "Default")
      (node (ref "IC3") (pin "5") (pinfunction "A4_5") (pintype "passive"))
      (node (ref "R11") (pin "2") (pinfunction "2_2") (pintype "passive"))
    )
    (net (code "114") (name "Net-(IC3-A5)") (class "Default")
      (node (ref "IC3") (pin "24") (pinfunction "A5_24") (pintype "passive"))
      (node (ref "R54") (pin "1") (pinfunction "1_1") (pintype "passive"))
    )
    (net (code "115") (name "Net-(IC3-~{OE})") (class "Default")
      (node (ref "IC3") (pin "23") (pinfunction "~{OE}_23") (pintype "passive"))
      (node (ref "R53") (pin "1") (pinfunction "1_1") (pintype "passive"))
    )
    (net (code "116") (name "Net-(IC4-IN--Pad2)") (class "Default")
      (node (ref "IC4") (pin "2") (pinfunction "IN-_2") (pintype "passive"))
      (node (ref "R29") (pin "2") (pinfunction "2_2") (pintype "passive"))
    )
    (net (code "117") (name "Net-(IC4-IN--Pad3)") (class "Default")
      (node (ref "IC4") (pin "3") (pinfunction "IN-_3") (pintype "passive"))
      (node (ref "R28") (pin "2") (pinfunction "2_2") (pintype "passive"))
    )
    (net (code "118") (name "Net-(IC5-IN--Pad2)") (class "Default")
      (node (ref "IC5") (pin "2") (pinfunction "IN-_2") (pintype "passive"))
      (node (ref "R31") (pin "2") (pinfunction "2_2") (pintype "passive"))
    )
    (net (code "119") (name "Net-(IC5-IN--Pad3)") (class "Default")
      (node (ref "IC5") (pin "3") (pinfunction "IN-_3") (pintype "passive"))
      (node (ref "R30") (pin "2") (pinfunction "2_2") (pintype "passive"))
    )
    (net (code "120") (name "Net-(IC6-IN--Pad2)") (class "Default")
      (node (ref "IC6") (pin "2") (pinfunction "IN-_2") (pintype "passive"))
      (node (ref "R33") (pin "2") (pinfunction "2_2") (pintype "passive"))
    )
    (net (code "121") (name "Net-(IC6-IN--Pad3)") (class "Default")
      (node (ref "IC6") (pin "3") (pinfunction "IN-_3") (pintype "passive"))
      (node (ref "R32") (pin "2") (pinfunction "2_2") (pintype "passive"))
    )
    (net (code "122") (name "Net-(IC7-IN--Pad2)") (class "Default")
      (node (ref "IC7") (pin "2") (pinfunction "IN-_2") (pintype "passive"))
      (node (ref "R35") (pin "2") (pinfunction "2_2") (pintype "passive"))
    )
    (net (code "123") (name "Net-(IC7-IN--Pad3)") (class "Default")
      (node (ref "IC7") (pin "3") (pinfunction "IN-_3") (pintype "passive"))
      (node (ref "R34") (pin "2") (pinfunction "2_2") (pintype "passive"))
    )
    (net (code "124") (name "Net-(IC8-IN--Pad2)") (class "Default")
      (node (ref "IC8") (pin "2") (pinfunction "IN-_2") (pintype "passive"))
      (node (ref "R64") (pin "2") (pinfunction "2_2") (pintype "passive"))
    )
    (net (code "125") (name "Net-(IC8-IN--Pad3)") (class "Default")
      (node (ref "IC8") (pin "3") (pinfunction "IN-_3") (pintype "passive"))
      (node (ref "R63") (pin "2") (pinfunction "2_2") (pintype "passive"))
    )
    (net (code "126") (name "Net-(IC9-IN--Pad2)") (class "Default")
      (node (ref "IC9") (pin "2") (pinfunction "IN-_2") (pintype "passive"))
      (node (ref "R66") (pin "2") (pinfunction "2_2") (pintype "passive"))
    )
    (net (code "127") (name "Net-(IC9-IN--Pad3)") (class "Default")
      (node (ref "IC9") (pin "3") (pinfunction "IN-_3") (pintype "passive"))
      (node (ref "R65") (pin "2") (pinfunction "2_2") (pintype "passive"))
    )
    (net (code "128") (name "Net-(IC10-IN--Pad2)") (class "Default")
      (node (ref "IC10") (pin "2") (pinfunction "IN-_2") (pintype "passive"))
      (node (ref "R68") (pin "2") (pinfunction "2_2") (pintype "passive"))
    )
    (net (code "129") (name "Net-(IC10-IN--Pad3)") (class "Default")
      (node (ref "IC10") (pin "3") (pinfunction "IN-_3") (pintype "passive"))
      (node (ref "R67") (pin "2") (pinfunction "2_2") (pintype "passive"))
    )
    (net (code "130") (name "Net-(IC11-IN--Pad2)") (class "Default")
      (node (ref "IC11") (pin "2") (pinfunction "IN-_2") (pintype "passive"))
      (node (ref "R70") (pin "2") (pinfunction "2_2") (pintype "passive"))
    )
    (net (code "131") (name "Net-(IC11-IN--Pad3)") (class "Default")
      (node (ref "IC11") (pin "3") (pinfunction "IN-_3") (pintype "passive"))
      (node (ref "R69") (pin "2") (pinfunction "2_2") (pintype "passive"))
    )
    (net (code "132") (name "Net-(IC12-DE)") (class "Default")
      (node (ref "IC12") (pin "2") (pinfunction "~{RE}_2") (pintype "passive"))
      (node (ref "IC12") (pin "3") (pinfunction "DE_3") (pintype "passive"))
      (node (ref "IC12") (pin "4") (pinfunction "DI_4") (pintype "passive"))
      (node (ref "R90") (pin "2") (pinfunction "2_2") (pintype "passive"))
    )
    (net (code "133") (name "Net-(IC13-DE)") (class "Default")
      (node (ref "IC13") (pin "2") (pinfunction "~{RE}_2") (pintype "passive"))
      (node (ref "IC13") (pin "3") (pinfunction "DE_3") (pintype "passive"))
      (node (ref "R89") (pin "2") (pinfunction "2_2") (pintype "passive"))
    )
    (net (code "134") (name "Net-(IC13-RO)") (class "Default")
      (node (ref "IC13") (pin "1") (pinfunction "RO_1") (pintype "passive"))
      (node (ref "R88") (pin "1") (pinfunction "1_1") (pintype "passive"))
    )
    (net (code "135") (name "Net-(JK1-Pad4)") (class "Default")
      (node (ref "JK1") (pin "4") (pinfunction "4_4") (pintype "passive"))
      (node (ref "JP12") (pin "1") (pinfunction "1_1") (pintype "passive"))
    )
    (net (code "136") (name "Net-(JK2-Pad4)") (class "Default")
      (node (ref "JK2") (pin "4") (pinfunction "4_4") (pintype "passive"))
      (node (ref "JP21") (pin "1") (pinfunction "1_1") (pintype "passive"))
    )
    (net (code "137") (name "Net-(LED1-A)") (class "Default")
      (node (ref "LED1") (pin "1") (pinfunction "A_1") (pintype "passive"))
      (node (ref "R44") (pin "1") (pinfunction "1_1") (pintype "passive"))
    )
    (net (code "138") (name "Net-(LED2-A)") (class "Default")
      (node (ref "LED2") (pin "1") (pinfunction "A_1") (pintype "passive"))
      (node (ref "R45") (pin "1") (pinfunction "1_1") (pintype "passive"))
    )
    (net (code "139") (name "Net-(LED3-A)") (class "Default")
      (node (ref "LED3") (pin "1") (pinfunction "A_1") (pintype "passive"))
      (node (ref "R46") (pin "1") (pinfunction "1_1") (pintype "passive"))
    )
    (net (code "140") (name "Net-(LED4-A)") (class "Default")
      (node (ref "LED4") (pin "1") (pinfunction "A_1") (pintype "passive"))
      (node (ref "R47") (pin "1") (pinfunction "1_1") (pintype "passive"))
    )
    (net (code "141") (name "Net-(LED5-A)") (class "Default")
      (node (ref "LED5") (pin "1") (pinfunction "A_1") (pintype "passive"))
      (node (ref "R48") (pin "1") (pinfunction "1_1") (pintype "passive"))
    )
    (net (code "142") (name "Net-(LED6-A)") (class "Default")
      (node (ref "LED6") (pin "1") (pinfunction "A_1") (pintype "passive"))
      (node (ref "R49") (pin "1") (pinfunction "1_1") (pintype "passive"))
    )
    (net (code "143") (name "Net-(LED7-A)") (class "Default")
      (node (ref "LED7") (pin "1") (pinfunction "A_1") (pintype "passive"))
      (node (ref "R50") (pin "1") (pinfunction "1_1") (pintype "passive"))
    )
    (net (code "144") (name "Net-(LED8-A)") (class "Default")
      (node (ref "LED8") (pin "1") (pinfunction "A_1") (pintype "passive"))
      (node (ref "R51") (pin "1") (pinfunction "1_1") (pintype "passive"))
    )
    (net (code "145") (name "Net-(LED9-A)") (class "Default")
      (node (ref "LED9") (pin "1") (pinfunction "A_1") (pintype "passive"))
      (node (ref "R52") (pin "1") (pinfunction "1_1") (pintype "passive"))
    )
    (net (code "146") (name "Net-(LED10-A)") (class "Default")
      (node (ref "LED10") (pin "1") (pinfunction "A_1") (pintype "passive"))
      (node (ref "R71") (pin "1") (pinfunction "1_1") (pintype "passive"))
    )
    (net (code "147") (name "Net-(LED11-A)") (class "Default")
      (node (ref "LED11") (pin "1") (pinfunction "A_1") (pintype "passive"))
      (node (ref "R73") (pin "1") (pinfunction "1_1") (pintype "passive"))
    )
    (net (code "148") (name "Net-(LED12-A)") (class "Default")
      (node (ref "LED12") (pin "1") (pinfunction "A_1") (pintype "passive"))
      (node (ref "R74") (pin "1") (pinfunction "1_1") (pintype "passive"))
    )
    (net (code "149") (name "Net-(LED13-A)") (class "Default")
      (node (ref "LED13") (pin "1") (pinfunction "A_1") (pintype "passive"))
      (node (ref "R75") (pin "1") (pinfunction "1_1") (pintype "passive"))
    )
    (net (code "150") (name "Net-(LED14-A)") (class "Default")
      (node (ref "LED14") (pin "1") (pinfunction "A_1") (pintype "passive"))
      (node (ref "R76") (pin "1") (pinfunction "1_1") (pintype "passive"))
    )
    (net (code "151") (name "Net-(LED15-A)") (class "Default")
      (node (ref "LED15") (pin "1") (pinfunction "A_1") (pintype "passive"))
      (node (ref "R77") (pin "1") (pinfunction "1_1") (pintype "passive"))
    )
    (net (code "152") (name "Net-(LED16-A)") (class "Default")
      (node (ref "LED16") (pin "1") (pinfunction "A_1") (pintype "passive"))
      (node (ref "R78") (pin "1") (pinfunction "1_1") (pintype "passive"))
    )
    (net (code "153") (name "Net-(M1-TRIM)") (class "Default")
      (node (ref "M1") (pin "5") (pinfunction "TRIM_5") (pintype "passive"))
      (node (ref "RP1") (pin "1") (pinfunction "1_1") (pintype "passive"))
      (node (ref "RP1") (pin "2") (pinfunction "2_2") (pintype "passive"))
    )
    (net (code "154") (name "Net-(M2-TRIM)") (class "Default")
      (node (ref "M2") (pin "5") (pinfunction "TRIM_5") (pintype "passive"))
      (node (ref "RP2") (pin "1") (pinfunction "1_1") (pintype "passive"))
      (node (ref "RP2") (pin "2") (pinfunction "2_2") (pintype "passive"))
    )
    (net (code "155") (name "Net-(M3-TRIM)") (class "Default")
      (node (ref "M3") (pin "5") (pinfunction "TRIM_5") (pintype "passive"))
      (node (ref "R10") (pin "1") (pinfunction "1_1") (pintype "passive"))
      (node (ref "R10") (pin "2") (pinfunction "2_2") (pintype "passive"))
    )
    (net (code "156") (name "Net-(M4-TRIM)") (class "Default")
      (node (ref "M4") (pin "5") (pinfunction "TRIM_5") (pintype "passive"))
      (node (ref "RP3") (pin "1") (pinfunction "1_1") (pintype "passive"))
      (node (ref "RP3") (pin "2") (pinfunction "2_2") (pintype "passive"))
    )
    (net (code "157") (name "Net-(M5-TRIM)") (class "Default")
      (node (ref "M5") (pin "5") (pinfunction "TRIM_5") (pintype "passive"))
      (node (ref "RP4") (pin "1") (pinfunction "1_1") (pintype "passive"))
      (node (ref "RP4") (pin "2") (pinfunction "2_2") (pintype "passive"))
    )
    (net (code "158") (name "Net-(M6-TRIM)") (class "Default")
      (node (ref "M6") (pin "5") (pinfunction "TRIM_5") (pintype "passive"))
      (node (ref "RP5") (pin "1") (pinfunction "1_1") (pintype "passive"))
      (node (ref "RP5") (pin "2") (pinfunction "2_2") (pintype "passive"))
    )
    (net (code "159") (name "Net-(Q1-B)") (class "Default")
      (node (ref "Q1") (pin "1") (pinfunction "B_1") (pintype "passive"))
      (node (ref "R72") (pin "2") (pinfunction "2_2") (pintype "passive"))
    )
    (net (code "160") (name "Net-(Q1-C)") (class "Default")
      (node (ref "JK1") (pin "1") (pinfunction "1_1") (pintype "passive"))
      (node (ref "Q1") (pin "3") (pinfunction "C_3") (pintype "passive"))
      (node (ref "VD4") (pin "1") (pinfunction "A_1") (pintype "passive"))
    )
    (net (code "161") (name "Net-(Q2-B)") (class "Default")
      (node (ref "Q2") (pin "1") (pinfunction "B_1") (pintype "passive"))
      (node (ref "R87") (pin "2") (pinfunction "2_2") (pintype "passive"))
    )
    (net (code "162") (name "Net-(Q2-C)") (class "Default")
      (node (ref "JK2") (pin "1") (pinfunction "1_1") (pintype "passive"))
      (node (ref "Q2") (pin "3") (pinfunction "C_3") (pintype "passive"))
      (node (ref "VD5") (pin "1") (pinfunction "A_1") (pintype "passive"))
    )
    (net (code "163") (name "Net-(U1-BOOT0)") (class "Default")
      (node (ref "R9") (pin "2") (pinfunction "2_2") (pintype "passive"))
      (node (ref "U1") (pin "44") (pinfunction "BOOT0_44") (pintype "input"))
    )
    (net (code "164") (name "Net-(U1-NRST)") (class "Default")
      (node (ref "C11") (pin "2") (pinfunction "2_2") (pintype "passive"))
      (node (ref "U1") (pin "7") (pinfunction "NRST_7") (pintype "bidirectional"))
    )
    (net (code "165") (name "Net-(U1-PA0-WKUP)") (class "Default")
      (node (ref "R5") (pin "2") (pinfunction "2_2") (pintype "passive"))
      (node (ref "R6") (pin "1") (pinfunction "1_1") (pintype "passive"))
      (node (ref "U1") (pin "10") (pinfunction "PA0-WKUP_10") (pintype "bidirectional"))
    )
    (net (code "166") (name "Net-(U1-PA11)") (class "Default")
      (node (ref "R8") (pin "2") (pinfunction "2_2") (pintype "passive"))
      (node (ref "U1") (pin "32") (pinfunction "PA11_32") (pintype "bidirectional"))
    )
    (net (code "167") (name "Net-(U1-PA12)") (class "Default")
      (node (ref "R7") (pin "2") (pinfunction "2_2") (pintype "passive"))
      (node (ref "U1") (pin "33") (pinfunction "PA12_33") (pintype "bidirectional"))
    )
    (net (code "168") (name "Net-(U1-PB3{slash}JTDO)") (class "Default")
      (node (ref "R16") (pin "1") (pinfunction "1_1") (pintype "passive"))
      (node (ref "U1") (pin "39") (pinfunction "PB3/JTDO_39") (pintype "bidirectional"))
    )
    (net (code "169") (name "Net-(U1-PC13-TAMPER-RTC)") (class "Default")
      (node (ref "R18") (pin "1") (pinfunction "1_1") (pintype "passive"))
      (node (ref "U1") (pin "2") (pinfunction "PC13-TAMPER-RTC_2") (pintype "bidirectional"))
    )
    (net (code "170") (name "Net-(U1-PC14-OSC32_IN)") (class "Default")
      (node (ref "R17") (pin "1") (pinfunction "1_1") (pintype "passive"))
      (node (ref "U1") (pin "3") (pinfunction "PC14-OSC32_IN_3") (pintype "bidirectional"))
    )
    (net (code "171") (name "Net-(U2-BOOT0)") (class "Default")
      (node (ref "R23") (pin "1") (pinfunction "1_1") (pintype "passive"))
      (node (ref "U2") (pin "94") (pinfunction "BOOT0_94") (pintype "passive"))
    )
    (net (code "172") (name "Net-(U2-NRST)") (class "Default")
      (node (ref "C51") (pin "2") (pinfunction "2_2") (pintype "passive"))
      (node (ref "R24") (pin "1") (pinfunction "1_1") (pintype "passive"))
      (node (ref "U2") (pin "14") (pinfunction "NRST_14") (pintype "passive"))
    )
    (net (code "173") (name "Net-(U2-OSC_IN)") (class "Default")
      (node (ref "C49") (pin "2") (pinfunction "2_2") (pintype "passive"))
      (node (ref "U2") (pin "12") (pinfunction "OSC_IN_12") (pintype "passive"))
      (node (ref "X4") (pin "1") (pinfunction "1_1") (pintype "passive"))
    )
    (net (code "174") (name "Net-(U2-OSC_OUT)") (class "Default")
      (node (ref "C50") (pin "2") (pinfunction "2_2") (pintype "passive"))
      (node (ref "U2") (pin "13") (pinfunction "OSC_OUT_13") (pintype "passive"))
      (node (ref "X4") (pin "2") (pinfunction "2_2") (pintype "passive"))
    )
    (net (code "175") (name "RPI_5V") (class "Default")
      (node (ref "E1") (pin "1") (pinfunction "A_1") (pintype "passive"))
      (node (ref "E2") (pin "1") (pinfunction "A_1") (pintype "passive"))
      (node (ref "JP20") (pin "2") (pinfunction "2_2") (pintype "passive"))
      (node (ref "JP20") (pin "4") (pinfunction "4_4") (pintype "passive"))
      (node (ref "JP20") (pin "6") (pinfunction "6_6") (pintype "passive"))
      (node (ref "JP20") (pin "8") (pinfunction "8_8") (pintype "passive"))
      (node (ref "M6") (pin "8") (pinfunction "VOUT_8") (pintype "passive"))
      (node (ref "R78") (pin "2") (pinfunction "2_2") (pintype "passive"))
    )
    (net (code "176") (name "SERVO_5V_1") (class "Default")
      (node (ref "E5") (pin "1") (pinfunction "A_1") (pintype "passive"))
      (node (ref "E6") (pin "1") (pinfunction "A_1") (pintype "passive"))
      (node (ref "JP15") (pin "1") (pinfunction "1_1") (pintype "passive"))
      (node (ref "JP15") (pin "3") (pinfunction "3_3") (pintype "passive"))
      (node (ref "JP15") (pin "5") (pinfunction "5_5") (pintype "passive"))
      (node (ref "JP15") (pin "7") (pinfunction "7_7") (pintype "passive"))
      (node (ref "JP8") (pin "11") (pinfunction "11_11") (pintype "passive"))
      (node (ref "JP8") (pin "12") (pinfunction "12_12") (pintype "passive"))
      (node (ref "M4") (pin "8") (pinfunction "VOUT_8") (pintype "passive"))
      (node (ref "R76") (pin "2") (pinfunction "2_2") (pintype "passive"))
      (node (ref "VD3") (pin "2") (pinfunction "K_2") (pintype "passive"))
    )
    (net (code "177") (name "SERVO_5V_2") (class "Default")
      (node (ref "E7") (pin "1") (pinfunction "A_1") (pintype "passive"))
      (node (ref "E8") (pin "1") (pinfunction "A_1") (pintype "passive"))
      (node (ref "JP14") (pin "1") (pinfunction "1_1") (pintype "passive"))
      (node (ref "JP14") (pin "3") (pinfunction "3_3") (pintype "passive"))
      (node (ref "JP14") (pin "5") (pinfunction "5_5") (pintype "passive"))
      (node (ref "JP14") (pin "7") (pinfunction "7_7") (pintype "passive"))
      (node (ref "JP8") (pin "13") (pinfunction "13_13") (pintype "passive"))
      (node (ref "JP8") (pin "14") (pinfunction "14_14") (pintype "passive"))
      (node (ref "M3") (pin "8") (pinfunction "VOUT_8") (pintype "passive"))
      (node (ref "R75") (pin "2") (pinfunction "2_2") (pintype "passive"))
      (node (ref "VD2") (pin "2") (pinfunction "K_2") (pintype "passive"))
    )
    (net (code "178") (name "SERVO_5V_3") (class "Default")
      (node (ref "E10") (pin "1") (pinfunction "A_1") (pintype "passive"))
      (node (ref "E9") (pin "1") (pinfunction "A_1") (pintype "passive"))
      (node (ref "JP13") (pin "1") (pinfunction "1_1") (pintype "passive"))
      (node (ref "JP13") (pin "3") (pinfunction "3_3") (pintype "passive"))
      (node (ref "JP13") (pin "5") (pinfunction "5_5") (pintype "passive"))
      (node (ref "JP13") (pin "7") (pinfunction "7_7") (pintype "passive"))
      (node (ref "JP8") (pin "15") (pinfunction "15_15") (pintype "passive"))
      (node (ref "JP8") (pin "16") (pinfunction "16_16") (pintype "passive"))
      (node (ref "M2") (pin "8") (pinfunction "VOUT_8") (pintype "passive"))
      (node (ref "R74") (pin "2") (pinfunction "2_2") (pintype "passive"))
      (node (ref "VD1") (pin "2") (pinfunction "K_2") (pintype "passive"))
    )
    (net (code "179") (name "SW_3V") (class "Default")
      (node (ref "C10") (pin "2") (pinfunction "2_2") (pintype "passive"))
      (node (ref "C8") (pin "2") (pinfunction "2_2") (pintype "passive"))
      (node (ref "JP17") (pin "4") (pinfunction "4_4") (pintype "passive"))
      (node (ref "R16") (pin "2") (pinfunction "2_2") (pintype "passive"))
      (node (ref "R44") (pin "2") (pinfunction "2_2") (pintype "passive"))
      (node (ref "R6") (pin "2") (pinfunction "2_2") (pintype "passive"))
      (node (ref "U1") (pin "24") (pinfunction "VDD_1_24") (pintype "power_in"))
      (node (ref "U1") (pin "36") (pinfunction "VDD_2_36") (pintype "power_in"))
      (node (ref "U1") (pin "48") (pinfunction "VDD_3_48") (pintype "power_in"))
      (node (ref "U1") (pin "9") (pinfunction "VDDA_9") (pintype "power_in"))
      (node (ref "V3") (pin "2") (pinfunction "Vout_2") (pintype "passive"))
    )
    (net (code "180") (name "unconnected-(IC1-CTS#-Pad9)") (class "Default")
      (node (ref "IC1") (pin "9") (pinfunction "CTS#_9") (pintype "passive"))
    )
    (net (code "181") (name "unconnected-(IC1-DCD#-Pad12)") (class "Default")
      (node (ref "IC1") (pin "12") (pinfunction "DCD#_12") (pintype "passive"))
    )
    (net (code "182") (name "unconnected-(IC1-DSR#-Pad10)") (class "Default")
      (node (ref "IC1") (pin "10") (pinfunction "DSR#_10") (pintype "passive"))
    )
    (net (code "183") (name "unconnected-(IC1-DTR#-Pad13)") (class "Default")
      (node (ref "IC1") (pin "13") (pinfunction "DTR#_13") (pintype "passive"))
    )
    (net (code "184") (name "unconnected-(IC1-RI#-Pad11)") (class "Default")
      (node (ref "IC1") (pin "11") (pinfunction "RI#_11") (pintype "passive"))
    )
    (net (code "185") (name "unconnected-(IC1-RS232-Pad15)") (class "Default")
      (node (ref "IC1") (pin "15") (pinfunction "RS232_15") (pintype "passive"))
    )
    (net (code "186") (name "unconnected-(IC1-RTS#-Pad14)") (class "Default")
      (node (ref "IC1") (pin "14") (pinfunction "RTS#_14") (pintype "passive"))
    )
    (net (code "187") (name "unconnected-(IC1-V3-Pad4)") (class "Default")
      (node (ref "IC1") (pin "4") (pinfunction "V3_4") (pintype "passive"))
    )
    (net (code "188") (name "unconnected-(IC2-PGANG-Pad18)") (class "Default")
      (node (ref "IC2") (pin "18") (pinfunction "PGANG_18") (pintype "passive"))
    )
    (net (code "189") (name "unconnected-(IC2-PSELF-Pad17)") (class "Default")
      (node (ref "IC2") (pin "17") (pinfunction "PSELF_17") (pintype "passive"))
    )
    (net (code "190") (name "unconnected-(IC2-PWREN1-Pad22)") (class "Default")
      (node (ref "IC2") (pin "22") (pinfunction "PWREN1_22") (pintype "passive"))
    )
    (net (code "191") (name "unconnected-(IC2-PWREN2-Pad20)") (class "Default")
      (node (ref "IC2") (pin "20") (pinfunction "PWREN2_20") (pintype "passive"))
    )
    (net (code "192") (name "unconnected-(IC2-TEST-Pad14)") (class "Default")
      (node (ref "IC2") (pin "14") (pinfunction "TEST_14") (pintype "passive"))
    )
    (net (code "193") (name "unconnected-(IC2-~{OVCUR1}-Pad21)") (class "Default")
      (node (ref "IC2") (pin "21") (pinfunction "~{OVCUR1}_21") (pintype "passive"))
    )
    (net (code "194") (name "unconnected-(IC2-~{OVCUR2}-Pad19)") (class "Default")
      (node (ref "IC2") (pin "19") (pinfunction "~{OVCUR2}_19") (pintype "passive"))
    )
    (net (code "195") (name "unconnected-(IC3-EXTCLK-Pad25)") (class "Default")
      (node (ref "IC3") (pin "25") (pinfunction "EXTCLK_25") (pintype "passive"))
    )
    (net (code "196") (name "unconnected-(JK1-Pad5)") (class "Default")
      (node (ref "JK1") (pin "5") (pinfunction "5_5") (pintype "passive"))
    )
    (net (code "197") (name "unconnected-(JK2-Pad5)") (class "Default")
      (node (ref "JK2") (pin "5") (pinfunction "5_5") (pintype "passive"))
    )
    (net (code "198") (name "unconnected-(JP8-Pad1)") (class "Default")
      (node (ref "JP8") (pin "1") (pinfunction "1_1") (pintype "passive"))
    )
    (net (code "199") (name "unconnected-(JP8-Pad2)") (class "Default")
      (node (ref "JP8") (pin "2") (pinfunction "2_2") (pintype "passive"))
    )
    (net (code "200") (name "unconnected-(JP8-Pad3)") (class "Default")
      (node (ref "JP8") (pin "3") (pinfunction "3_3") (pintype "passive"))
    )
    (net (code "201") (name "unconnected-(JP8-Pad4)") (class "Default")
      (node (ref "JP8") (pin "4") (pinfunction "4_4") (pintype "passive"))
    )
    (net (code "202") (name "unconnected-(JP8-Pad5)") (class "Default")
      (node (ref "JP8") (pin "5") (pinfunction "5_5") (pintype "passive"))
    )
    (net (code "203") (name "unconnected-(JP8-Pad6)") (class "Default")
      (node (ref "JP8") (pin "6") (pinfunction "6_6") (pintype "passive"))
    )
    (net (code "204") (name "unconnected-(JP8-Pad7)") (class "Default")
      (node (ref "JP8") (pin "7") (pinfunction "7_7") (pintype "passive"))
    )
    (net (code "205") (name "unconnected-(JP8-Pad8)") (class "Default")
      (node (ref "JP8") (pin "8") (pinfunction "8_8") (pintype "passive"))
    )
    (net (code "206") (name "unconnected-(JP8-Pad9)") (class "Default")
      (node (ref "JP8") (pin "9") (pinfunction "9_9") (pintype "passive"))
    )
    (net (code "207") (name "unconnected-(JP8-Pad10)") (class "Default")
      (node (ref "JP8") (pin "10") (pinfunction "10_10") (pintype "passive"))
    )
    (net (code "208") (name "unconnected-(M1-POWER_GOOD-Pad6)") (class "Default")
      (node (ref "M1") (pin "6") (pinfunction "POWER_GOOD_6") (pintype "passive"))
    )
    (net (code "209") (name "unconnected-(M1-PSV{slash}PSS-Pad4)") (class "Default")
      (node (ref "M1") (pin "4") (pinfunction "PSV/PSS_4") (pintype "passive"))
    )
    (net (code "210") (name "unconnected-(M1-REMOTE-Pad3)") (class "Default")
      (node (ref "M1") (pin "3") (pinfunction "REMOTE_3") (pintype "passive"))
    )
    (net (code "211") (name "unconnected-(M2-POWER_GOOD-Pad6)") (class "Default")
      (node (ref "M2") (pin "6") (pinfunction "POWER_GOOD_6") (pintype "passive"))
    )
    (net (code "212") (name "unconnected-(M2-PSV{slash}PSS-Pad4)") (class "Default")
      (node (ref "M2") (pin "4") (pinfunction "PSV/PSS_4") (pintype "passive"))
    )
    (net (code "213") (name "unconnected-(M2-REMOTE-Pad3)") (class "Default")
      (node (ref "M2") (pin "3") (pinfunction "REMOTE_3") (pintype "passive"))
    )
    (net (code "214") (name "unconnected-(M3-POWER_GOOD-Pad6)") (class "Default")
      (node (ref "M3") (pin "6") (pinfunction "POWER_GOOD_6") (pintype "passive"))
    )
    (net (code "215") (name "unconnected-(M3-PSV{slash}PSS-Pad4)") (class "Default")
      (node (ref "M3") (pin "4") (pinfunction "PSV/PSS_4") (pintype "passive"))
    )
    (net (code "216") (name "unconnected-(M3-REMOTE-Pad3)") (class "Default")
      (node (ref "M3") (pin "3") (pinfunction "REMOTE_3") (pintype "passive"))
    )
    (net (code "217") (name "unconnected-(M4-POWER_GOOD-Pad6)") (class "Default")
      (node (ref "M4") (pin "6") (pinfunction "POWER_GOOD_6") (pintype "passive"))
    )
    (net (code "218") (name "unconnected-(M4-PSV{slash}PSS-Pad4)") (class "Default")
      (node (ref "M4") (pin "4") (pinfunction "PSV/PSS_4") (pintype "passive"))
    )
    (net (code "219") (name "unconnected-(M4-REMOTE-Pad3)") (class "Default")
      (node (ref "M4") (pin "3") (pinfunction "REMOTE_3") (pintype "passive"))
    )
    (net (code "220") (name "unconnected-(M5-POWER_GOOD-Pad6)") (class "Default")
      (node (ref "M5") (pin "6") (pinfunction "POWER_GOOD_6") (pintype "passive"))
    )
    (net (code "221") (name "unconnected-(M5-PSV{slash}PSS-Pad4)") (class "Default")
      (node (ref "M5") (pin "4") (pinfunction "PSV/PSS_4") (pintype "passive"))
    )
    (net (code "222") (name "unconnected-(M5-REMOTE-Pad3)") (class "Default")
      (node (ref "M5") (pin "3") (pinfunction "REMOTE_3") (pintype "passive"))
    )
    (net (code "223") (name "unconnected-(M6-POWER_GOOD-Pad6)") (class "Default")
      (node (ref "M6") (pin "6") (pinfunction "POWER_GOOD_6") (pintype "passive"))
    )
    (net (code "224") (name "unconnected-(M6-PSV{slash}PSS-Pad4)") (class "Default")
      (node (ref "M6") (pin "4") (pinfunction "PSV/PSS_4") (pintype "passive"))
    )
    (net (code "225") (name "unconnected-(M6-REMOTE-Pad3)") (class "Default")
      (node (ref "M6") (pin "3") (pinfunction "REMOTE_3") (pintype "passive"))
    )
    (net (code "226") (name "unconnected-(U1-PA1-Pad11)") (class "Default")
      (node (ref "U1") (pin "11") (pinfunction "PA1_11") (pintype "bidirectional"))
    )
    (net (code "227") (name "unconnected-(U1-PA2-Pad12)") (class "Default")
      (node (ref "U1") (pin "12") (pinfunction "PA2_12") (pintype "bidirectional"))
    )
    (net (code "228") (name "unconnected-(U1-PA3-Pad13)") (class "Default")
      (node (ref "U1") (pin "13") (pinfunction "PA3_13") (pintype "bidirectional"))
    )
    (net (code "229") (name "unconnected-(U1-PA4-Pad14)") (class "Default")
      (node (ref "U1") (pin "14") (pinfunction "PA4_14") (pintype "bidirectional"))
    )
    (net (code "230") (name "unconnected-(U1-PA5-Pad15)") (class "Default")
      (node (ref "U1") (pin "15") (pinfunction "PA5_15") (pintype "bidirectional"))
    )
    (net (code "231") (name "unconnected-(U1-PA6-Pad16)") (class "Default")
      (node (ref "U1") (pin "16") (pinfunction "PA6_16") (pintype "bidirectional"))
    )
    (net (code "232") (name "unconnected-(U1-PA7-Pad17)") (class "Default")
      (node (ref "U1") (pin "17") (pinfunction "PA7_17") (pintype "bidirectional"))
    )
    (net (code "233") (name "unconnected-(U1-PA8-Pad29)") (class "Default")
      (node (ref "U1") (pin "29") (pinfunction "PA8_29") (pintype "bidirectional"))
    )
    (net (code "234") (name "unconnected-(U1-PA10-Pad31)") (class "Default")
      (node (ref "U1") (pin "31") (pinfunction "PA10_31") (pintype "bidirectional"))
    )
    (net (code "235") (name "unconnected-(U1-PA15{slash}JTDI-Pad38)") (class "Default")
      (node (ref "U1") (pin "38") (pinfunction "PA15/JTDI_38") (pintype "bidirectional"))
    )
    (net (code "236") (name "unconnected-(U1-PB0-Pad18)") (class "Default")
      (node (ref "U1") (pin "18") (pinfunction "PB0_18") (pintype "bidirectional"))
    )
    (net (code "237") (name "unconnected-(U1-PB1-Pad19)") (class "Default")
      (node (ref "U1") (pin "19") (pinfunction "PB1_19") (pintype "bidirectional"))
    )
    (net (code "238") (name "unconnected-(U1-PB4{slash}JNTRST-Pad40)") (class "Default")
      (node (ref "U1") (pin "40") (pinfunction "PB4/JNTRST_40") (pintype "bidirectional"))
    )
    (net (code "239") (name "unconnected-(U1-PB5-Pad41)") (class "Default")
      (node (ref "U1") (pin "41") (pinfunction "PB5_41") (pintype "bidirectional"))
    )
    (net (code "240") (name "unconnected-(U1-PB6-Pad42)") (class "Default")
      (node (ref "U1") (pin "42") (pinfunction "PB6_42") (pintype "bidirectional"))
    )
    (net (code "241") (name "unconnected-(U1-PB7-Pad43)") (class "Default")
      (node (ref "U1") (pin "43") (pinfunction "PB7_43") (pintype "bidirectional"))
    )
    (net (code "242") (name "unconnected-(U1-PB8-Pad45)") (class "Default")
      (node (ref "U1") (pin "45") (pinfunction "PB8_45") (pintype "bidirectional"))
    )
    (net (code "243") (name "unconnected-(U1-PB9-Pad46)") (class "Default")
      (node (ref "U1") (pin "46") (pinfunction "PB9_46") (pintype "bidirectional"))
    )
    (net (code "244") (name "unconnected-(U1-PB10-Pad21)") (class "Default")
      (node (ref "U1") (pin "21") (pinfunction "PB10_21") (pintype "bidirectional"))
    )
    (net (code "245") (name "unconnected-(U1-PB11-Pad22)") (class "Default")
      (node (ref "U1") (pin "22") (pinfunction "PB11_22") (pintype "bidirectional"))
    )
    (net (code "246") (name "unconnected-(U1-PC15-OSC32_OUT-Pad4)") (class "Default")
      (node (ref "U1") (pin "4") (pinfunction "PC15-OSC32_OUT_4") (pintype "bidirectional"))
    )
    (net (code "247") (name "unconnected-(U1-VBAT-Pad1)") (class "Default")
      (node (ref "U1") (pin "1") (pinfunction "VBAT_1") (pintype "power_in"))
    )
    (net (code "248") (name "unconnected-(U2-NC-Pad73)") (class "Default")
      (node (ref "U2") (pin "73") (pinfunction "NC_73") (pintype "passive"))
    )
    (net (code "249") (name "unconnected-(U2-PA0{slash}WKUP{slash}ADC123_IN0{slash}T2C1ETR{slash}T5C1{slash}T8ETR-Pad23)") (class "Default")
      (node (ref "U2") (pin "23") (pinfunction "PA0/WKUP/ADC123_IN0/T2C1ETR/T5C1/T8ETR_23") (pintype "passive"))
    )
    (net (code "250") (name "unconnected-(U2-PA1{slash}ADC123_IN1{slash}T5C2{slash}T2C2-Pad24)") (class "Default")
      (node (ref "U2") (pin "24") (pinfunction "PA1/ADC123_IN1/T5C2/T2C2_24") (pintype "passive"))
    )
    (net (code "251") (name "unconnected-(U2-PA15{slash}JTDI{slash}I2S3_WS{slash}JTDI{slash}T2C1ETR{slash}SPI3_NSS-Pad77)") (class "Default")
      (node (ref "U2") (pin "77") (pinfunction "PA15/JTDI/I2S3_WS/JTDI/T2C1ETR/SPI3_NSS_77") (pintype "passive"))
    )
    (net (code "252") (name "unconnected-(U2-PB8{slash}SDIO_D4{slash}I2C1_SCL{slash}T4C3(7){slash}CAN_Rx-Pad95)") (class "Default")
      (node (ref "U2") (pin "95") (pinfunction "PB8/SDIO_D4/I2C1_SCL/T4C3(7)/CAN_Rx_95") (pintype "passive"))
    )
    (net (code "253") (name "unconnected-(U2-PB9{slash}SDIO_D5{slash}I2C1_SDA{slash}T4C4{slash}CAN_Tx-Pad96)") (class "Default")
      (node (ref "U2") (pin "96") (pinfunction "PB9/SDIO_D5/I2C1_SDA/T4C4/CAN_Tx_96") (pintype "passive"))
    )
    (net (code "254") (name "unconnected-(U2-PC0{slash}ADC123_IN10-Pad15)") (class "Default")
      (node (ref "U2") (pin "15") (pinfunction "PC0/ADC123_IN10_15") (pintype "passive"))
    )
    (net (code "255") (name "unconnected-(U2-PC1{slash}ADC123_IN11-Pad16)") (class "Default")
      (node (ref "U2") (pin "16") (pinfunction "PC1/ADC123_IN11_16") (pintype "passive"))
    )
    (net (code "256") (name "unconnected-(U2-PC2{slash}ADC123_IN12-Pad17)") (class "Default")
      (node (ref "U2") (pin "17") (pinfunction "PC2/ADC123_IN12_17") (pintype "passive"))
    )
    (net (code "257") (name "unconnected-(U2-PC3{slash}ADC123_IN13-Pad18)") (class "Default")
      (node (ref "U2") (pin "18") (pinfunction "PC3/ADC123_IN13_18") (pintype "passive"))
    )
    (net (code "258") (name "unconnected-(U2-PC4{slash}ADC123_IN14-Pad33)") (class "Default")
      (node (ref "U2") (pin "33") (pinfunction "PC4/ADC123_IN14_33") (pintype "passive"))
    )
    (net (code "259") (name "unconnected-(U2-PC5{slash}ADC123_IN15-Pad34)") (class "Default")
      (node (ref "U2") (pin "34") (pinfunction "PC5/ADC123_IN15_34") (pintype "passive"))
    )
    (net (code "260") (name "unconnected-(U2-PC6{slash}I2S2_MCK{slash}T8C1{slash}T3C1{slash}SDIO_D6-Pad63)") (class "Default")
      (node (ref "U2") (pin "63") (pinfunction "PC6/I2S2_MCK/T8C1/T3C1/SDIO_D6_63") (pintype "passive"))
    )
    (net (code "261") (name "unconnected-(U2-PC7{slash}I2S3_MCK{slash}T8C2{slash}T3C2{slash}SDIO_D7-Pad64)") (class "Default")
      (node (ref "U2") (pin "64") (pinfunction "PC7/I2S3_MCK/T8C2/T3C2/SDIO_D7_64") (pintype "passive"))
    )
    (net (code "262") (name "unconnected-(U2-PC8{slash}T8C3{slash}T3C3{slash}SDIO_D0-Pad65)") (class "Default")
      (node (ref "U2") (pin "65") (pinfunction "PC8/T8C3/T3C3/SDIO_D0_65") (pintype "passive"))
    )
    (net (code "263") (name "unconnected-(U2-PC9{slash}T8C4{slash}T3C4{slash}SDIO_D1-Pad66)") (class "Default")
      (node (ref "U2") (pin "66") (pinfunction "PC9/T8C4/T3C4/SDIO_D1_66") (pintype "passive"))
    )
    (net (code "264") (name "unconnected-(U2-PC12{slash}UART5_Tx{slash}SDIO_CK-Pad80)") (class "Default")
      (node (ref "U2") (pin "80") (pinfunction "PC12/UART5_Tx/SDIO_CK_80") (pintype "passive"))
    )
    (net (code "265") (name "unconnected-(U2-PC13-TAMPER-RTC-Pad7)") (class "Default")
      (node (ref "U2") (pin "7") (pinfunction "PC13-TAMPER-RTC_7") (pintype "passive"))
    )
    (net (code "266") (name "unconnected-(U2-PC14-OSC32_IN-Pad8)") (class "Default")
      (node (ref "U2") (pin "8") (pinfunction "PC14-OSC32_IN_8") (pintype "passive"))
    )
    (net (code "267") (name "unconnected-(U2-PC15-OSC32_OUT-Pad9)") (class "Default")
      (node (ref "U2") (pin "9") (pinfunction "PC15-OSC32_OUT_9") (pintype "passive"))
    )
    (net (code "268") (name "unconnected-(U2-PD0{slash}CAN_Rx{slash}FSMC_D2-Pad81)") (class "Default")
      (node (ref "U2") (pin "81") (pinfunction "PD0/CAN_Rx/FSMC_D2_81") (pintype "passive"))
    )
    (net (code "269") (name "unconnected-(U2-PD1{slash}CAN_Tx{slash}FSMC_D3-Pad82)") (class "Default")
      (node (ref "U2") (pin "82") (pinfunction "PD1/CAN_Tx/FSMC_D3_82") (pintype "passive"))
    )
    (net (code "270") (name "unconnected-(U2-PD2{slash}UART5_Rx{slash}T3ETR{slash}SDIO_CMD-Pad83)") (class "Default")
      (node (ref "U2") (pin "83") (pinfunction "PD2/UART5_Rx/T3ETR/SDIO_CMD_83") (pintype "passive"))
    )
    (net (code "271") (name "unconnected-(U2-PD3{slash}FSMC_CLK-Pad84)") (class "Default")
      (node (ref "U2") (pin "84") (pinfunction "PD3/FSMC_CLK_84") (pintype "passive"))
    )
    (net (code "272") (name "unconnected-(U2-PD4{slash}FSMC_NOE-Pad85)") (class "Default")
      (node (ref "U2") (pin "85") (pinfunction "PD4/FSMC_NOE_85") (pintype "passive"))
    )
    (net (code "273") (name "unconnected-(U2-PD5{slash}USART2_Tx{slash}FSMC_NWE-Pad86)") (class "Default")
      (node (ref "U2") (pin "86") (pinfunction "PD5/USART2_Tx/FSMC_NWE_86") (pintype "passive"))
    )
    (net (code "274") (name "unconnected-(U2-PD6{slash}USART2_Rx{slash}FSMC_NWAIT-Pad87)") (class "Default")
      (node (ref "U2") (pin "87") (pinfunction "PD6/USART2_Rx/FSMC_NWAIT_87") (pintype "passive"))
    )
    (net (code "275") (name "unconnected-(U2-PD7{slash}FSMC_NE1{slash}FSMC_NCE2-Pad88)") (class "Default")
      (node (ref "U2") (pin "88") (pinfunction "PD7/FSMC_NE1/FSMC_NCE2_88") (pintype "passive"))
    )
    (net (code "276") (name "unconnected-(U2-PD10{slash}FSMC_D15-Pad57)") (class "Default")
      (node (ref "U2") (pin "57") (pinfunction "PD10/FSMC_D15_57") (pintype "passive"))
    )
    (net (code "277") (name "unconnected-(U2-PD11{slash}FSMC_A16-Pad58)") (class "Default")
      (node (ref "U2") (pin "58") (pinfunction "PD11/FSMC_A16_58") (pintype "passive"))
    )
    (net (code "278") (name "unconnected-(U2-PD12{slash}T4C1{slash}FSMC_A17-Pad59)") (class "Default")
      (node (ref "U2") (pin "59") (pinfunction "PD12/T4C1/FSMC_A17_59") (pintype "passive"))
    )
    (net (code "279") (name "unconnected-(U2-PD13{slash}T4C2{slash}FSMC_A18-Pad60)") (class "Default")
      (node (ref "U2") (pin "60") (pinfunction "PD13/T4C2/FSMC_A18_60") (pintype "passive"))
    )
    (net (code "280") (name "unconnected-(U2-PD14{slash}T4C3{slash}FSMC_D0-Pad61)") (class "Default")
      (node (ref "U2") (pin "61") (pinfunction "PD14/T4C3/FSMC_D0_61") (pintype "passive"))
    )
    (net (code "281") (name "unconnected-(U2-PD15{slash}T4C4{slash}FSMC_D1-Pad62)") (class "Default")
      (node (ref "U2") (pin "62") (pinfunction "PD15/T4C4/FSMC_D1_62") (pintype "passive"))
    )
    (net (code "282") (name "unconnected-(U2-PE0{slash}T4_ETR{slash}FSMC_NBL0-Pad97)") (class "Default")
      (node (ref "U2") (pin "97") (pinfunction "PE0/T4_ETR/FSMC_NBL0_97") (pintype "passive"))
    )
    (net (code "283") (name "unconnected-(U2-PE1{slash}FSMC_NBL1-Pad98)") (class "Default")
      (node (ref "U2") (pin "98") (pinfunction "PE1/FSMC_NBL1_98") (pintype "passive"))
    )
    (net (code "284") (name "unconnected-(U2-PE2{slash}TRACECK{slash}RSMC_A23-Pad1)") (class "Default")
      (node (ref "U2") (pin "1") (pinfunction "PE2/TRACECK/RSMC_A23_1") (pintype "passive"))
    )
    (net (code "285") (name "unconnected-(U2-PE3{slash}TRACED0{slash}FSMC_A19-Pad2)") (class "Default")
      (node (ref "U2") (pin "2") (pinfunction "PE3/TRACED0/FSMC_A19_2") (pintype "passive"))
    )
    (net (code "286") (name "unconnected-(U2-PE4{slash}TRACED1{slash}FSMC_A20-Pad3)") (class "Default")
      (node (ref "U2") (pin "3") (pinfunction "PE4/TRACED1/FSMC_A20_3") (pintype "passive"))
    )
    (net (code "287") (name "unconnected-(U2-PE5{slash}TRACED2{slash}FSMC_A21-Pad4)") (class "Default")
      (node (ref "U2") (pin "4") (pinfunction "PE5/TRACED2/FSMC_A21_4") (pintype "passive"))
    )
    (net (code "288") (name "unconnected-(U2-PE6{slash}TRACED3{slash}FSMC_A22-Pad5)") (class "Default")
      (node (ref "U2") (pin "5") (pinfunction "PE6/TRACED3/FSMC_A22_5") (pintype "passive"))
    )
    (net (code "289") (name "unconnected-(U2-PE7{slash}FSMC_D4{slash}T1ETR-Pad38)") (class "Default")
      (node (ref "U2") (pin "38") (pinfunction "PE7/FSMC_D4/T1ETR_38") (pintype "passive"))
    )
    (net (code "290") (name "unconnected-(U2-PE8{slash}FSMC_D5{slash}T1CH1N-Pad39)") (class "Default")
      (node (ref "U2") (pin "39") (pinfunction "PE8/FSMC_D5/T1CH1N_39") (pintype "passive"))
    )
    (net (code "291") (name "unconnected-(U2-PE9{slash}FSMC_D6{slash}T1C1-Pad40)") (class "Default")
      (node (ref "U2") (pin "40") (pinfunction "PE9/FSMC_D6/T1C1_40") (pintype "passive"))
    )
    (net (code "292") (name "unconnected-(U2-PE10{slash}FSMC_D7{slash}T1CH2N-Pad41)") (class "Default")
      (node (ref "U2") (pin "41") (pinfunction "PE10/FSMC_D7/T1CH2N_41") (pintype "passive"))
    )
    (net (code "293") (name "unconnected-(U2-PE11{slash}FSMC_D8{slash}T1C2-Pad42)") (class "Default")
      (node (ref "U2") (pin "42") (pinfunction "PE11/FSMC_D8/T1C2_42") (pintype "passive"))
    )
    (net (code "294") (name "unconnected-(U2-PE12{slash}FSMC_D9{slash}T1CH3N-Pad43)") (class "Default")
      (node (ref "U2") (pin "43") (pinfunction "PE12/FSMC_D9/T1CH3N_43") (pintype "passive"))
    )
    (net (code "295") (name "unconnected-(U2-PE13{slash}FSMC_D10{slash}T1C3-Pad44)") (class "Default")
      (node (ref "U2") (pin "44") (pinfunction "PE13/FSMC_D10/T1C3_44") (pintype "passive"))
    )
    (net (code "296") (name "unconnected-(U2-PE14{slash}FSMC_D11{slash}T1C4-Pad45)") (class "Default")
      (node (ref "U2") (pin "45") (pinfunction "PE14/FSMC_D11/T1C4_45") (pintype "passive"))
    )
    (net (code "297") (name "unconnected-(U2-PE15{slash}FSMC_D12{slash}T1BKIN-Pad46)") (class "Default")
      (node (ref "U2") (pin "46") (pinfunction "PE15/FSMC_D12/T1BKIN_46") (pintype "passive"))
    )
    (net (code "298") (name "unconnected-(U2-VBAT-Pad6)") (class "Default")
      (node (ref "U2") (pin "6") (pinfunction "VBAT_6") (pintype "passive"))
    )
    (net (code "299") (name "unconnected-(USB1-+5V-Pad1)") (class "Default")
      (node (ref "USB1") (pin "1") (pinfunction "+5V_1") (pintype "passive"))
    )
    (net (code "300") (name "unconnected-(USB1-ID-Pad4)") (class "Default")
      (node (ref "USB1") (pin "4") (pinfunction "ID_4") (pintype "passive"))
    )
  )
)
